# Hocki-Control.net
KiCad netlist of a schematic drawn in EAGLE
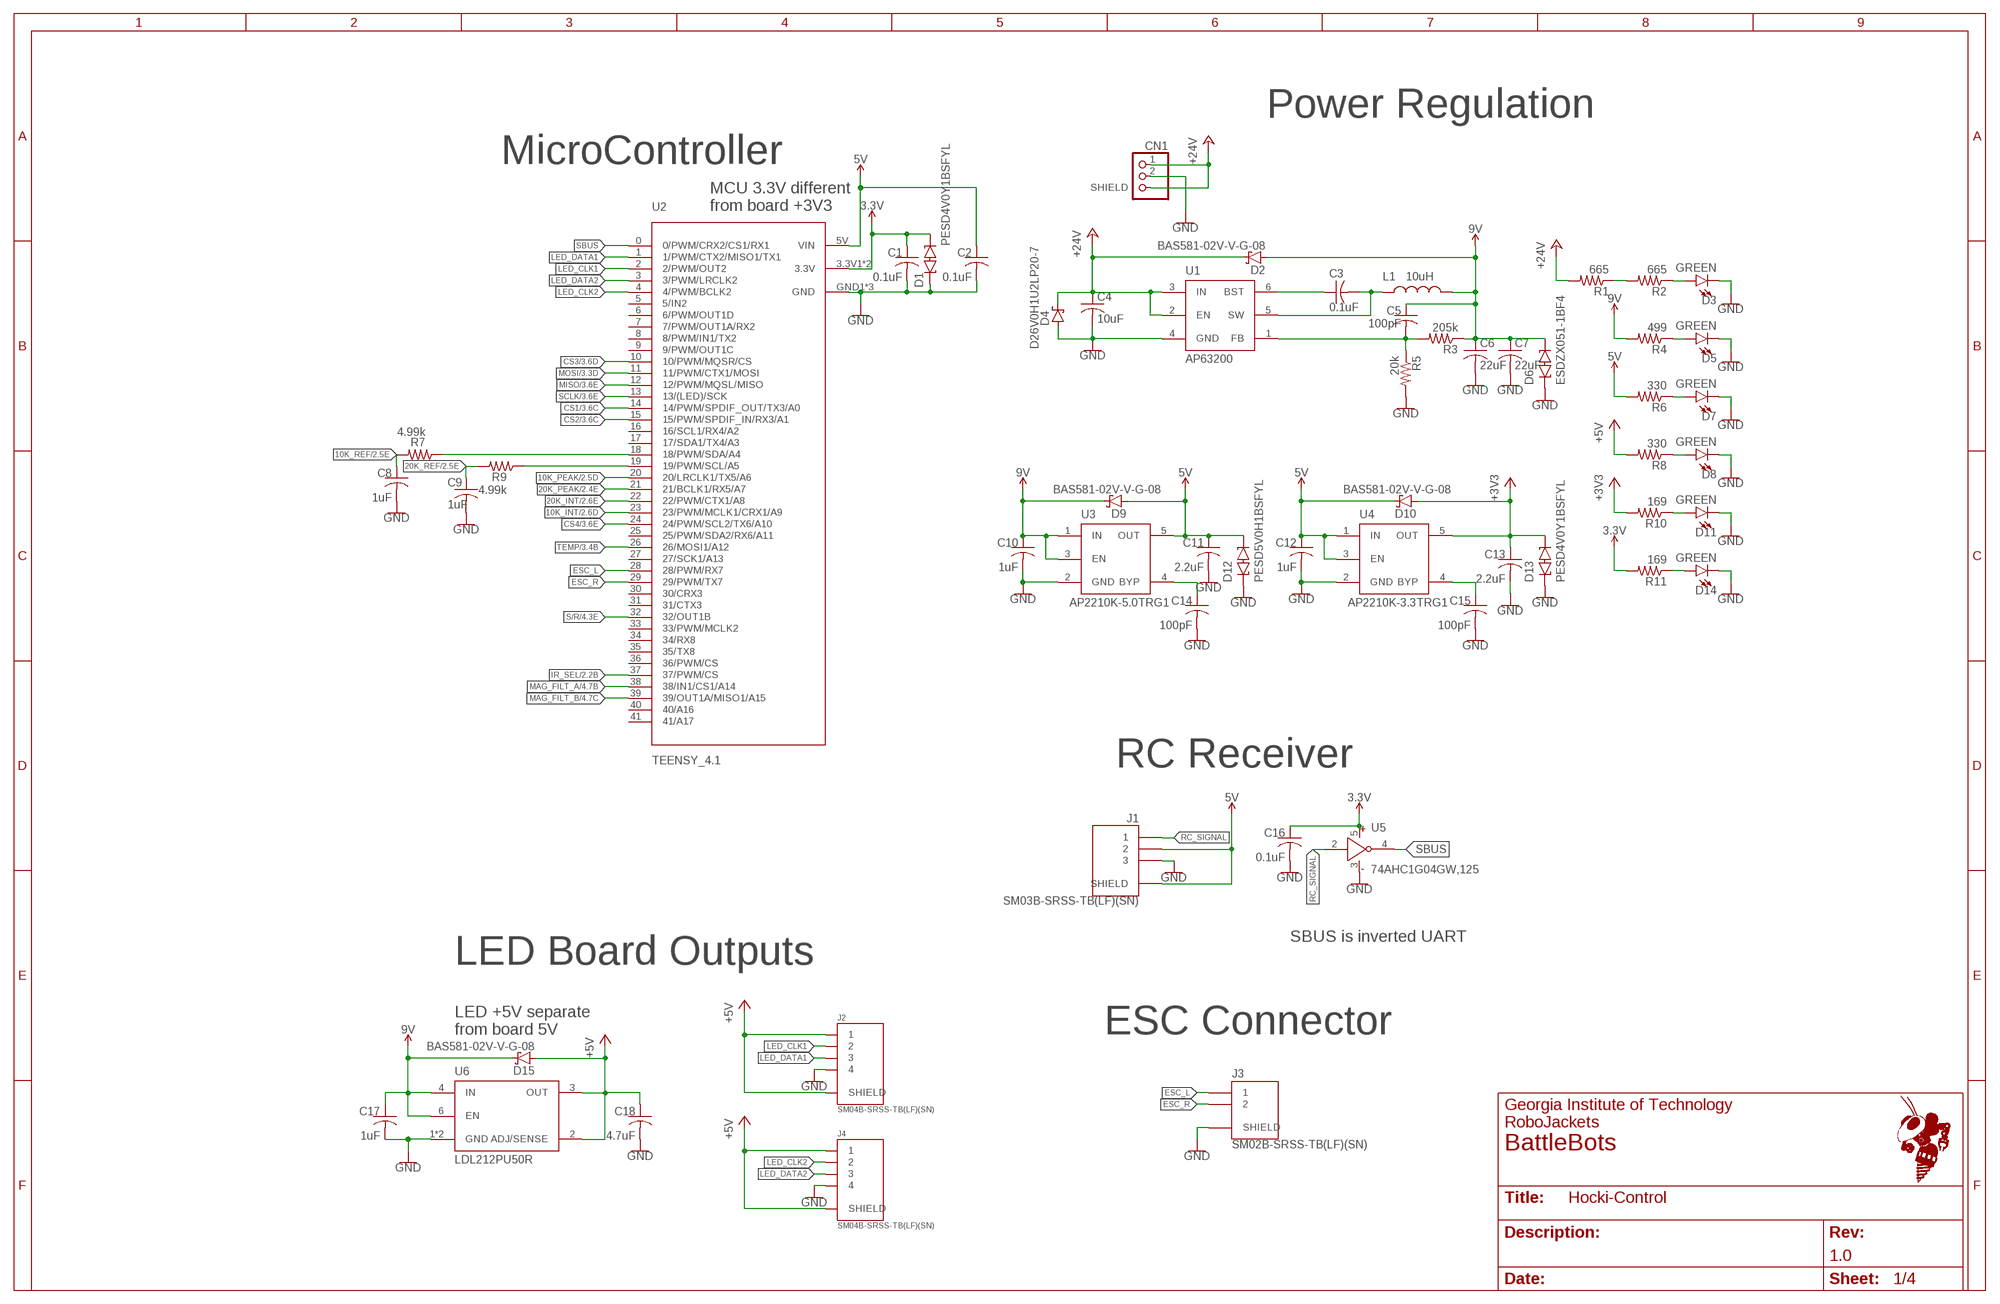
[diagram p0: schematic, sheet 1]
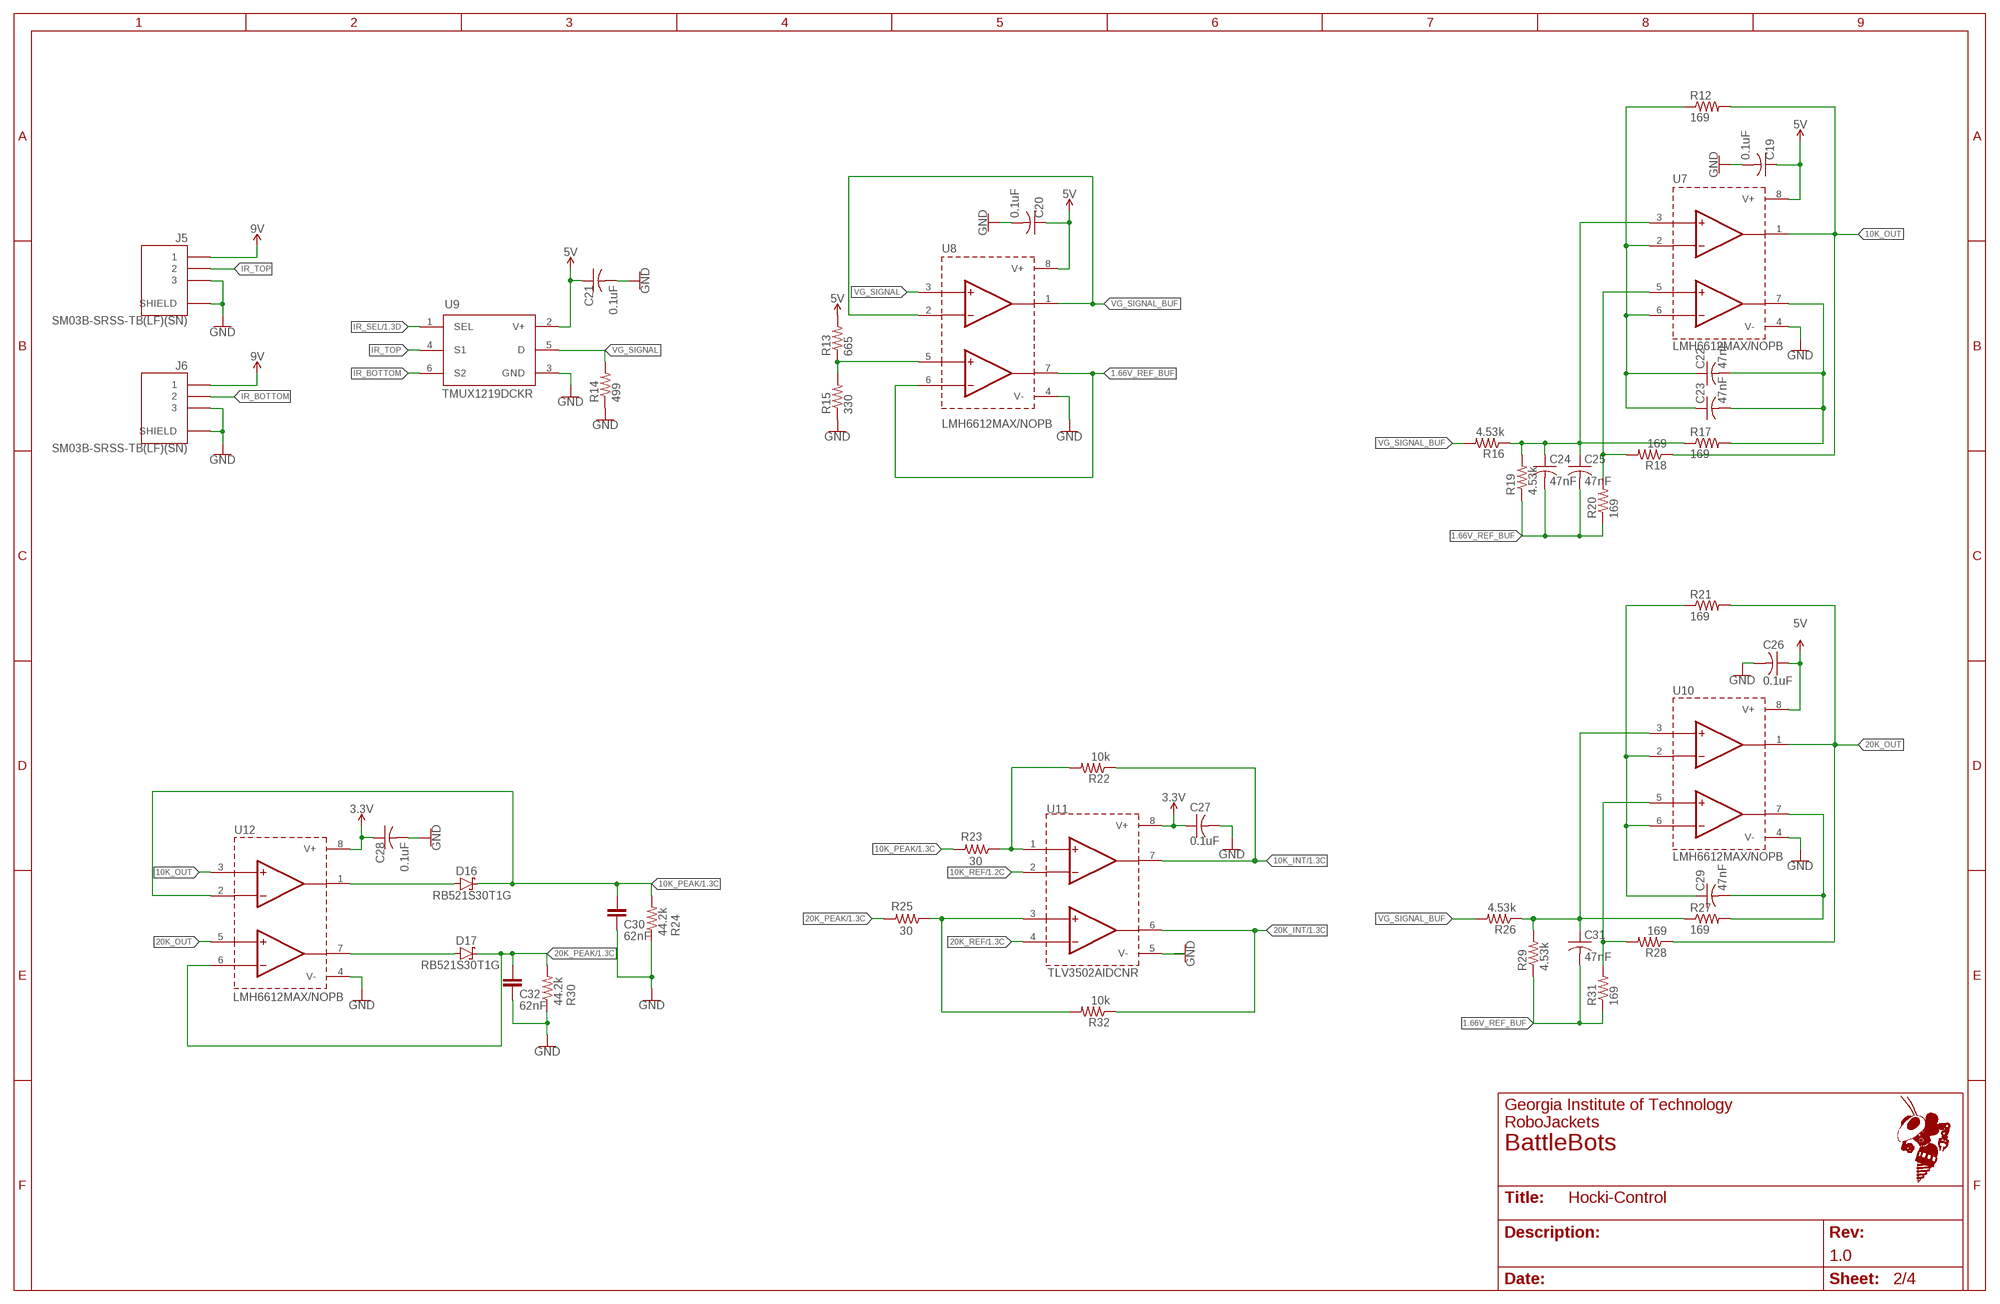
[diagram p1: schematic, sheet 2]
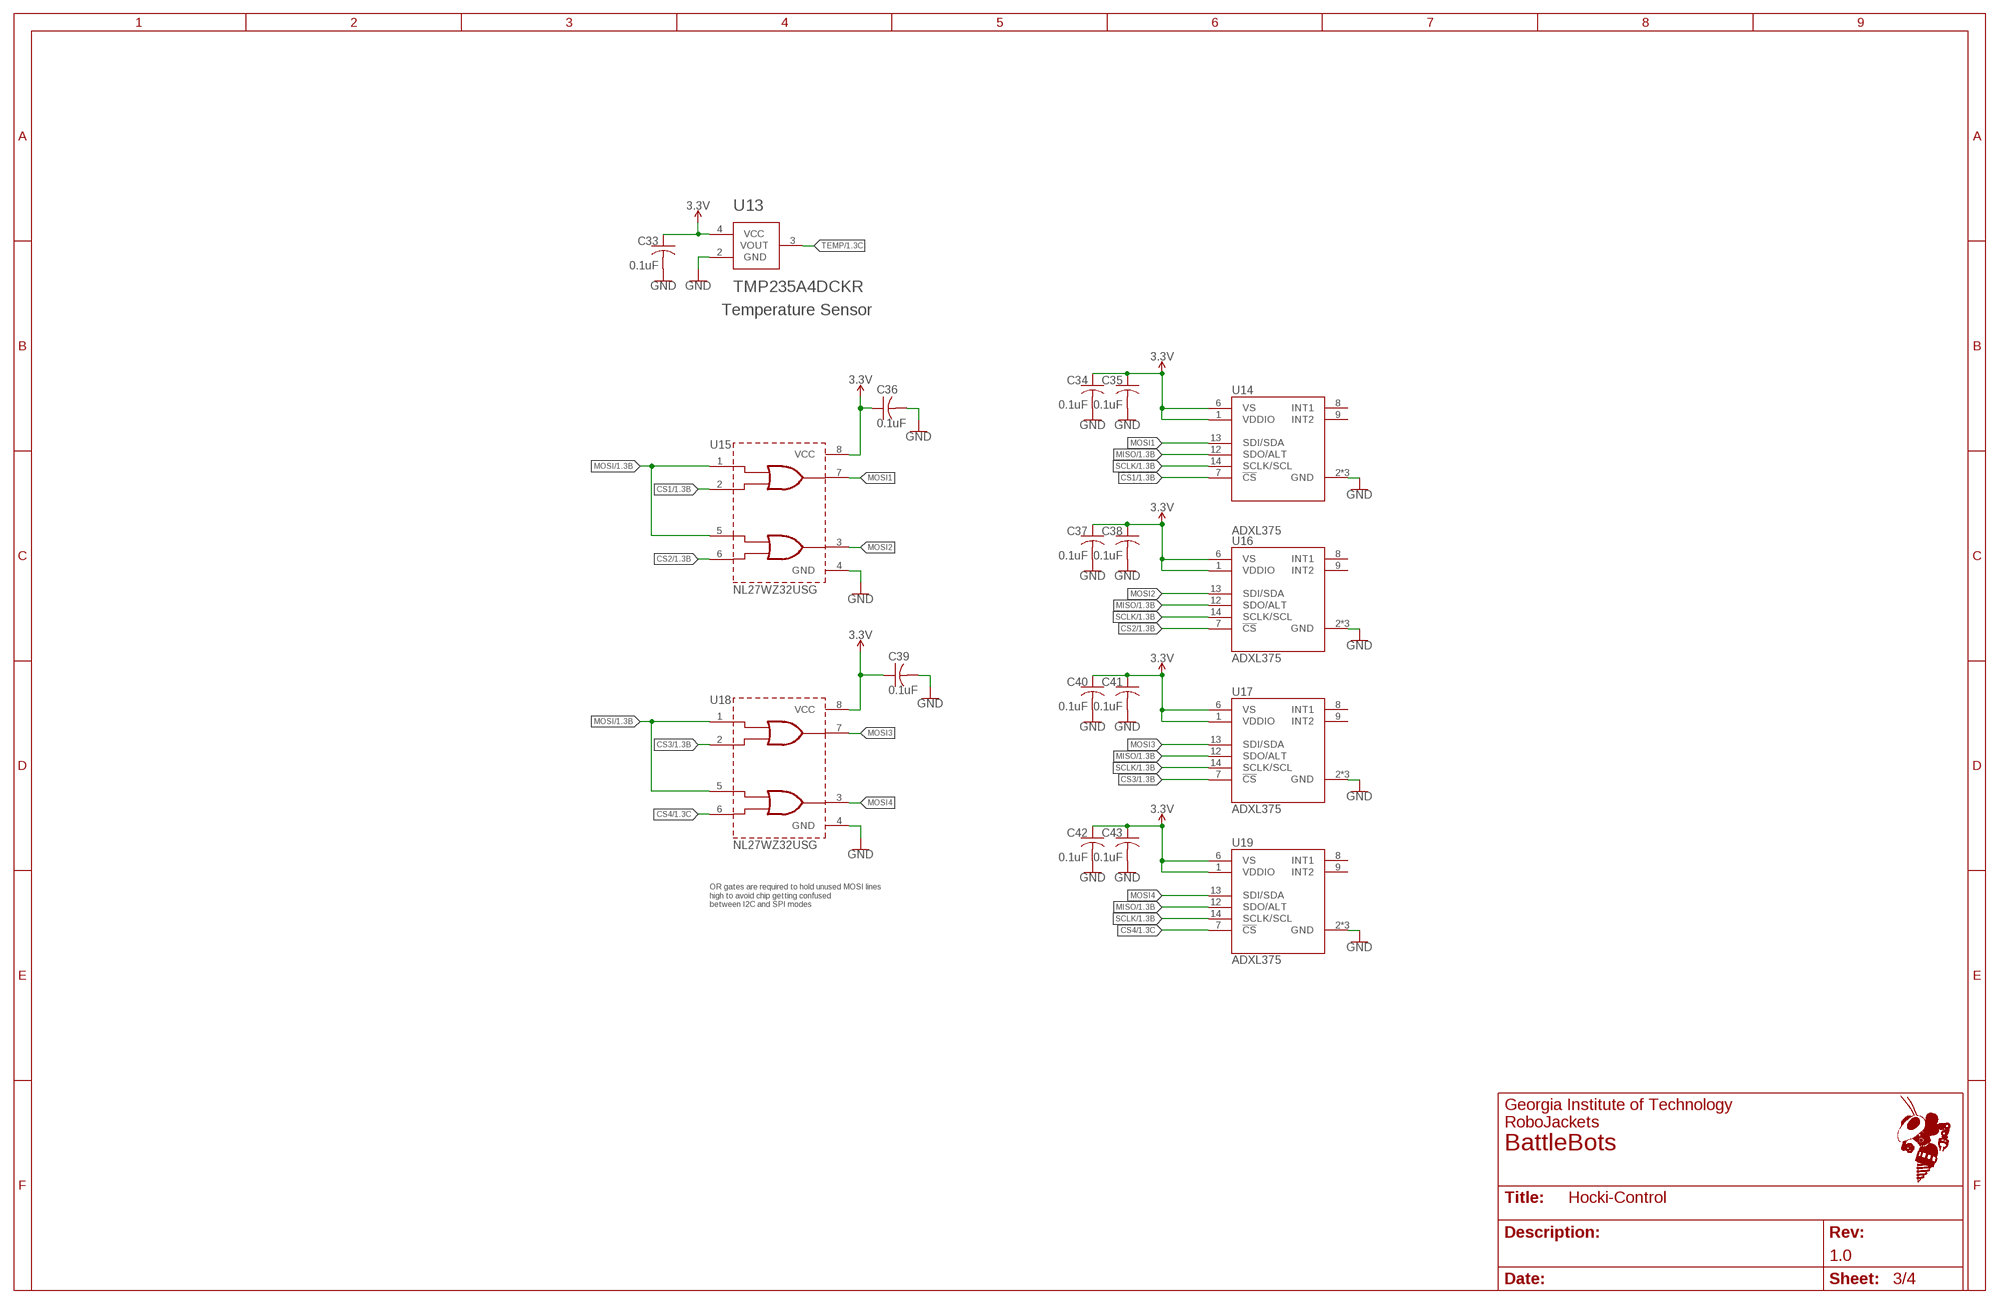
[diagram p2: schematic, sheet 3]
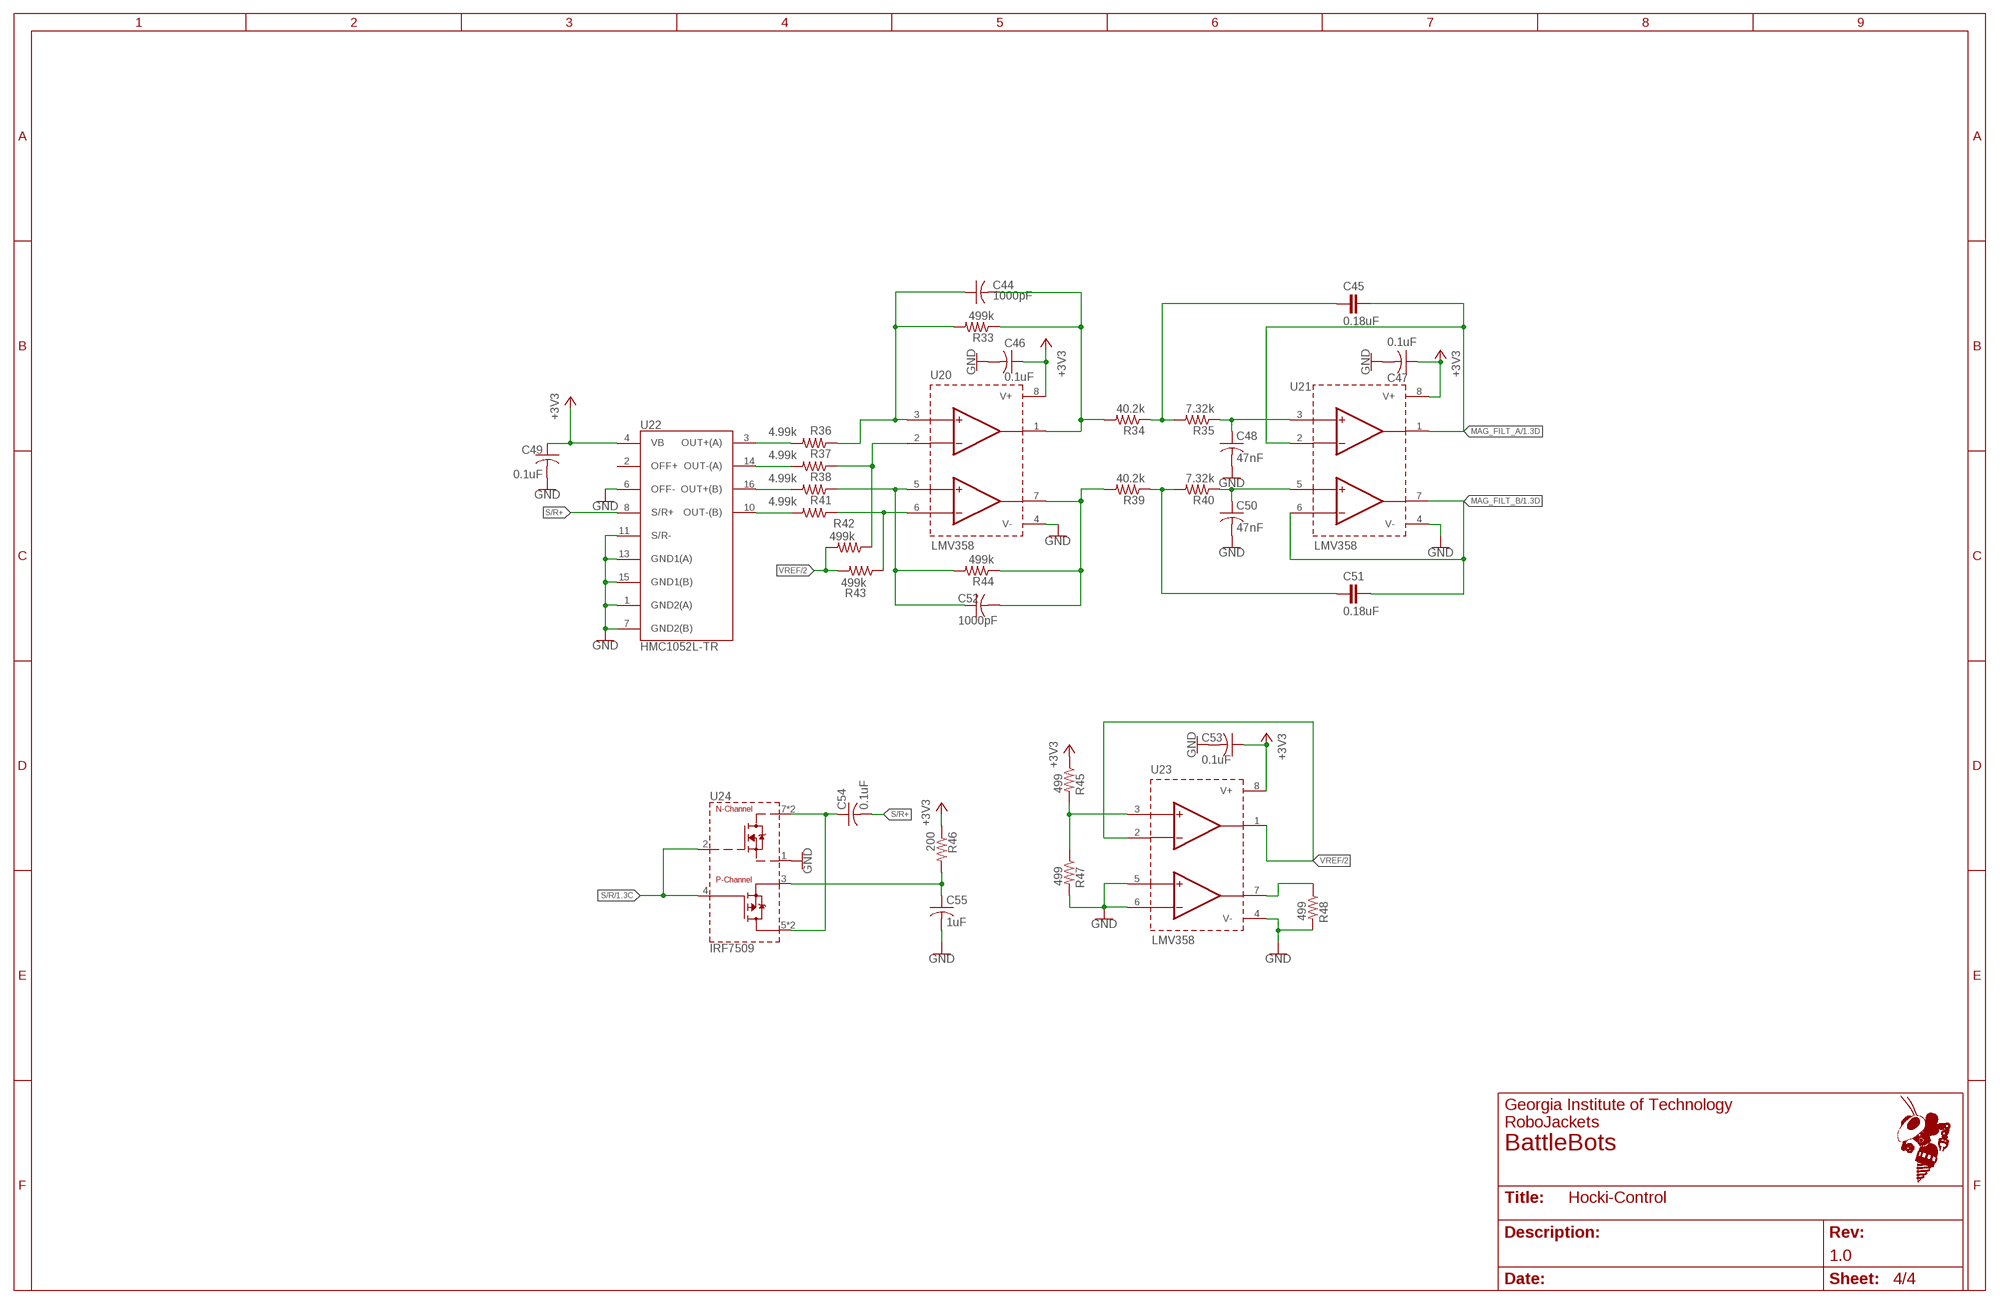
[diagram p3: schematic, sheet 4]

(export (version "E")
  (design (tool "Eeschema 10.0.6"))
  (components
    (comp (ref "C19")
      (value "0.1uF")
      (footprint "eagle-import:C0603")
      (libsource (lib "eagle-import") (part "C-USC0603"))
    )
    (comp (ref "C20")
      (value "0.1uF")
      (footprint "eagle-import:C0603")
      (libsource (lib "eagle-import") (part "C-USC0603"))
    )
    (comp (ref "C21")
      (value "0.1uF")
      (footprint "eagle-import:C0603")
      (libsource (lib "eagle-import") (part "C-USC0603"))
    )
    (comp (ref "C22")
      (value "47nF")
      (footprint "eagle-import:C1206")
      (libsource (lib "eagle-import") (part "C-USC1206"))
    )
    (comp (ref "C23")
      (value "47nF")
      (footprint "eagle-import:C1206")
      (libsource (lib "eagle-import") (part "C-USC1206"))
    )
    (comp (ref "C24")
      (value "47nF")
      (footprint "eagle-import:C1206")
      (libsource (lib "eagle-import") (part "C-USC1206"))
    )
    (comp (ref "C25")
      (value "47nF")
      (footprint "eagle-import:C1206")
      (libsource (lib "eagle-import") (part "C-USC1206"))
    )
    (comp (ref "C26")
      (value "0.1uF")
      (footprint "eagle-import:C0603")
      (libsource (lib "eagle-import") (part "C-USC0603"))
    )
    (comp (ref "C27")
      (value "0.1uF")
      (footprint "eagle-import:C0603")
      (libsource (lib "eagle-import") (part "C-USC0603"))
    )
    (comp (ref "C28")
      (value "0.1uF")
      (footprint "eagle-import:C0603")
      (libsource (lib "eagle-import") (part "C-USC0603"))
    )
    (comp (ref "C29")
      (value "47nF")
      (footprint "eagle-import:C1206")
      (libsource (lib "eagle-import") (part "C-USC1206"))
    )
    (comp (ref "C30")
      (value "62nF")
      (footprint "eagle-import:BFC241646203")
      (libsource (lib "eagle-import") (part "BFC241646203"))
    )
    (comp (ref "C31")
      (value "47nF")
      (footprint "eagle-import:C1206")
      (libsource (lib "eagle-import") (part "C-USC1206"))
    )
    (comp (ref "C32")
      (value "62nF")
      (footprint "eagle-import:BFC241646203")
      (libsource (lib "eagle-import") (part "BFC241646203"))
    )
    (comp (ref "D16")
      (value "RB521S30T1G")
      (footprint "eagle-import:SOD-523")
      (libsource (lib "eagle-import") (part "RB521S30T1G"))
    )
    (comp (ref "D17")
      (value "RB521S30T1G")
      (footprint "eagle-import:SOD-523")
      (libsource (lib "eagle-import") (part "RB521S30T1G"))
    )
    (comp (ref "J5")
      (value "SM03B-SRSS-TB(LF)(SN)")
      (footprint "eagle-import:SM03B-SRSS-TB(LF)(SN)")
      (libsource (lib "eagle-import") (part "SM03B-SRSS-TB(LF)(SN)"))
    )
    (comp (ref "J6")
      (value "SM03B-SRSS-TB(LF)(SN)")
      (footprint "eagle-import:SM03B-SRSS-TB(LF)(SN)")
      (libsource (lib "eagle-import") (part "SM03B-SRSS-TB(LF)(SN)"))
    )
    (comp (ref "R12")
      (value "169")
      (footprint "eagle-import:R0603")
      (libsource (lib "eagle-import") (part "R-US_R0603"))
    )
    (comp (ref "R13")
      (value "665")
      (footprint "eagle-import:R0603")
      (libsource (lib "eagle-import") (part "R-US_R0603"))
    )
    (comp (ref "R14")
      (value "499")
      (footprint "eagle-import:R0603")
      (libsource (lib "eagle-import") (part "R-US_R0603"))
    )
    (comp (ref "R15")
      (value "330")
      (footprint "eagle-import:R0603")
      (libsource (lib "eagle-import") (part "R-US_R0603"))
    )
    (comp (ref "R16")
      (value "4.53k")
      (footprint "eagle-import:R0603")
      (libsource (lib "eagle-import") (part "R-US_R0603"))
    )
    (comp (ref "R17")
      (value "169")
      (footprint "eagle-import:R0603")
      (libsource (lib "eagle-import") (part "R-US_R0603"))
    )
    (comp (ref "R18")
      (value "169")
      (footprint "eagle-import:R0603")
      (libsource (lib "eagle-import") (part "R-US_R0603"))
    )
    (comp (ref "R19")
      (value "4.53k")
      (footprint "eagle-import:R0603")
      (libsource (lib "eagle-import") (part "R-US_R0603"))
    )
    (comp (ref "R20")
      (value "169")
      (footprint "eagle-import:R0603")
      (libsource (lib "eagle-import") (part "R-US_R0603"))
    )
    (comp (ref "R21")
      (value "169")
      (footprint "eagle-import:R0603")
      (libsource (lib "eagle-import") (part "R-US_R0603"))
    )
    (comp (ref "R22")
      (value "10k")
      (footprint "eagle-import:R0603")
      (libsource (lib "eagle-import") (part "R-US_R0603"))
    )
    (comp (ref "R23")
      (value "30")
      (footprint "eagle-import:R0603")
      (libsource (lib "eagle-import") (part "R-US_R0603"))
    )
    (comp (ref "R24")
      (value "44.2k")
      (footprint "eagle-import:R0603")
      (libsource (lib "eagle-import") (part "R-US_R0603"))
    )
    (comp (ref "R25")
      (value "30")
      (footprint "eagle-import:R0603")
      (libsource (lib "eagle-import") (part "R-US_R0603"))
    )
    (comp (ref "R26")
      (value "4.53k")
      (footprint "eagle-import:R0603")
      (libsource (lib "eagle-import") (part "R-US_R0603"))
    )
    (comp (ref "R27")
      (value "169")
      (footprint "eagle-import:R0603")
      (libsource (lib "eagle-import") (part "R-US_R0603"))
    )
    (comp (ref "R28")
      (value "169")
      (footprint "eagle-import:R0603")
      (libsource (lib "eagle-import") (part "R-US_R0603"))
    )
    (comp (ref "R29")
      (value "4.53k")
      (footprint "eagle-import:R0603")
      (libsource (lib "eagle-import") (part "R-US_R0603"))
    )
    (comp (ref "R30")
      (value "44.2k")
      (footprint "eagle-import:R0603")
      (libsource (lib "eagle-import") (part "R-US_R0603"))
    )
    (comp (ref "R31")
      (value "169")
      (footprint "eagle-import:R0603")
      (libsource (lib "eagle-import") (part "R-US_R0603"))
    )
    (comp (ref "R32")
      (value "10k")
      (footprint "eagle-import:R0603")
      (libsource (lib "eagle-import") (part "R-US_R0603"))
    )
    (comp (ref "U7")
      (value "LMH6612MAX/NOPB")
      (footprint "eagle-import:8-SOIC")
      (libsource (lib "eagle-import") (part "LMH6612MAX/NOPB"))
    )
    (comp (ref "U8")
      (value "LMH6612MAX/NOPB")
      (footprint "eagle-import:8-SOIC")
      (libsource (lib "eagle-import") (part "LMH6612MAX/NOPB"))
    )
    (comp (ref "U9")
      (value "TMUX1219DCKR")
      (footprint "eagle-import:SOT-363")
      (libsource (lib "eagle-import") (part "TMUX1219DCKR"))
    )
    (comp (ref "U10")
      (value "LMH6612MAX/NOPB")
      (footprint "eagle-import:8-SOIC")
      (libsource (lib "eagle-import") (part "LMH6612MAX/NOPB"))
    )
    (comp (ref "U11")
      (value "TLV3502AIDCNR")
      (footprint "eagle-import:SOT-23-8")
      (libsource (lib "eagle-import") (part "TLV3502AIDCNR"))
    )
    (comp (ref "U12")
      (value "LMH6612MAX/NOPB")
      (footprint "eagle-import:8-SOIC")
      (libsource (lib "eagle-import") (part "LMH6612MAX/NOPB"))
    )
    (comp (ref "C44")
      (value "1000pF")
      (footprint "eagle-import:C0805")
      (libsource (lib "eagle-import") (part "C-USC0805"))
    )
    (comp (ref "C45")
      (value "0.18uF")
      (footprint "eagle-import:ECH-U1H184GX9")
      (libsource (lib "eagle-import") (part "ECH-U1H184GX9"))
    )
    (comp (ref "C46")
      (value "0.1uF")
      (footprint "eagle-import:C0603")
      (libsource (lib "eagle-import") (part "C-USC0603"))
    )
    (comp (ref "C47")
      (value "0.1uF")
      (footprint "eagle-import:C0603")
      (libsource (lib "eagle-import") (part "C-USC0603"))
    )
    (comp (ref "C48")
      (value "47nF")
      (footprint "eagle-import:C1206")
      (libsource (lib "eagle-import") (part "C-USC1206"))
    )
    (comp (ref "C49")
      (value "0.1uF")
      (footprint "eagle-import:C0603")
      (libsource (lib "eagle-import") (part "C-USC0603"))
    )
    (comp (ref "C50")
      (value "47nF")
      (footprint "eagle-import:C1206")
      (libsource (lib "eagle-import") (part "C-USC1206"))
    )
    (comp (ref "C51")
      (value "0.18uF")
      (footprint "eagle-import:ECH-U1H184GX9")
      (libsource (lib "eagle-import") (part "ECH-U1H184GX9"))
    )
    (comp (ref "C52")
      (value "1000pF")
      (footprint "eagle-import:C0805")
      (libsource (lib "eagle-import") (part "C-USC0805"))
    )
    (comp (ref "C53")
      (value "0.1uF")
      (footprint "eagle-import:C0603")
      (libsource (lib "eagle-import") (part "C-USC0603"))
    )
    (comp (ref "C54")
      (value "0.1uF")
      (footprint "eagle-import:C0603")
      (libsource (lib "eagle-import") (part "C-USC0603"))
    )
    (comp (ref "C55")
      (value "1uF")
      (footprint "eagle-import:C0603")
      (libsource (lib "eagle-import") (part "C-USC0603"))
    )
    (comp (ref "R33")
      (value "499k")
      (footprint "eagle-import:R0603")
      (libsource (lib "eagle-import") (part "R-US_R0603"))
    )
    (comp (ref "R34")
      (value "40.2k")
      (footprint "eagle-import:R0603")
      (libsource (lib "eagle-import") (part "R-US_R0603"))
    )
    (comp (ref "R35")
      (value "7.32k")
      (footprint "eagle-import:R0603")
      (libsource (lib "eagle-import") (part "R-US_R0603"))
    )
    (comp (ref "R36")
      (value "4.99k")
      (footprint "eagle-import:R0603")
      (libsource (lib "eagle-import") (part "R-US_R0603"))
    )
    (comp (ref "R37")
      (value "4.99k")
      (footprint "eagle-import:R0603")
      (libsource (lib "eagle-import") (part "R-US_R0603"))
    )
    (comp (ref "R38")
      (value "4.99k")
      (footprint "eagle-import:R0603")
      (libsource (lib "eagle-import") (part "R-US_R0603"))
    )
    (comp (ref "R39")
      (value "40.2k")
      (footprint "eagle-import:R0603")
      (libsource (lib "eagle-import") (part "R-US_R0603"))
    )
    (comp (ref "R40")
      (value "7.32k")
      (footprint "eagle-import:R0603")
      (libsource (lib "eagle-import") (part "R-US_R0603"))
    )
    (comp (ref "R41")
      (value "4.99k")
      (footprint "eagle-import:R0603")
      (libsource (lib "eagle-import") (part "R-US_R0603"))
    )
    (comp (ref "R42")
      (value "499k")
      (footprint "eagle-import:R0603")
      (libsource (lib "eagle-import") (part "R-US_R0603"))
    )
    (comp (ref "R43")
      (value "499k")
      (footprint "eagle-import:R0603")
      (libsource (lib "eagle-import") (part "R-US_R0603"))
    )
    (comp (ref "R44")
      (value "499k")
      (footprint "eagle-import:R0603")
      (libsource (lib "eagle-import") (part "R-US_R0603"))
    )
    (comp (ref "R45")
      (value "499")
      (footprint "eagle-import:R0603")
      (libsource (lib "eagle-import") (part "R-US_R0603"))
    )
    (comp (ref "R46")
      (value "200")
      (footprint "eagle-import:R0603")
      (libsource (lib "eagle-import") (part "R-US_R0603"))
    )
    (comp (ref "R47")
      (value "499")
      (footprint "eagle-import:R0603")
      (libsource (lib "eagle-import") (part "R-US_R0603"))
    )
    (comp (ref "R48")
      (value "499")
      (footprint "eagle-import:R0603")
      (libsource (lib "eagle-import") (part "R-US_R0603"))
    )
    (comp (ref "U20")
      (value "LMV358")
      (footprint "eagle-import:8-SOIC")
      (libsource (lib "eagle-import") (part "LMV358"))
    )
    (comp (ref "U21")
      (value "LMV358")
      (footprint "eagle-import:8-SOIC")
      (libsource (lib "eagle-import") (part "LMV358"))
    )
    (comp (ref "U22")
      (value "HMC1052L-TR")
      (footprint "eagle-import:16-LCC")
      (libsource (lib "eagle-import") (part "HMC1052L-TR"))
    )
    (comp (ref "U23")
      (value "LMV358")
      (footprint "eagle-import:8-SOIC")
      (libsource (lib "eagle-import") (part "LMV358"))
    )
    (comp (ref "U24")
      (value "IRF7509")
      (footprint "eagle-import:MICRO8")
      (libsource (lib "eagle-import") (part "IRF7509"))
    )
    (comp (ref "C33")
      (value "0.1uF")
      (footprint "eagle-import:C0603")
      (libsource (lib "eagle-import") (part "C-USC0603"))
    )
    (comp (ref "C34")
      (value "0.1uF")
      (footprint "eagle-import:C0603")
      (libsource (lib "eagle-import") (part "C-USC0603"))
    )
    (comp (ref "C35")
      (value "0.1uF")
      (footprint "eagle-import:C0603")
      (libsource (lib "eagle-import") (part "C-USC0603"))
    )
    (comp (ref "C36")
      (value "0.1uF")
      (footprint "eagle-import:C0603")
      (libsource (lib "eagle-import") (part "C-USC0603"))
    )
    (comp (ref "C37")
      (value "0.1uF")
      (footprint "eagle-import:C0603")
      (libsource (lib "eagle-import") (part "C-USC0603"))
    )
    (comp (ref "C38")
      (value "0.1uF")
      (footprint "eagle-import:C0603")
      (libsource (lib "eagle-import") (part "C-USC0603"))
    )
    (comp (ref "C39")
      (value "0.1uF")
      (footprint "eagle-import:C0603")
      (libsource (lib "eagle-import") (part "C-USC0603"))
    )
    (comp (ref "C40")
      (value "0.1uF")
      (footprint "eagle-import:C0603")
      (libsource (lib "eagle-import") (part "C-USC0603"))
    )
    (comp (ref "C41")
      (value "0.1uF")
      (footprint "eagle-import:C0603")
      (libsource (lib "eagle-import") (part "C-USC0603"))
    )
    (comp (ref "C42")
      (value "0.1uF")
      (footprint "eagle-import:C0603")
      (libsource (lib "eagle-import") (part "C-USC0603"))
    )
    (comp (ref "C43")
      (value "0.1uF")
      (footprint "eagle-import:C0603")
      (libsource (lib "eagle-import") (part "C-USC0603"))
    )
    (comp (ref "U13")
      (value "TMP235A4DCKR")
      (footprint "eagle-import:SOT-353")
      (libsource (lib "eagle-import") (part "TMP235A4DCKR"))
    )
    (comp (ref "U14")
      (value "ADXL375")
      (footprint "eagle-import:14-LGA")
      (libsource (lib "eagle-import") (part "ADXL375"))
    )
    (comp (ref "U15")
      (value "NL27WZ32USG")
      (footprint "eagle-import:US8")
      (libsource (lib "eagle-import") (part "NL27WZ32USG"))
    )
    (comp (ref "U16")
      (value "ADXL375")
      (footprint "eagle-import:14-LGA")
      (libsource (lib "eagle-import") (part "ADXL375"))
    )
    (comp (ref "U17")
      (value "ADXL375")
      (footprint "eagle-import:14-LGA")
      (libsource (lib "eagle-import") (part "ADXL375"))
    )
    (comp (ref "U18")
      (value "NL27WZ32USG")
      (footprint "eagle-import:US8")
      (libsource (lib "eagle-import") (part "NL27WZ32USG"))
    )
    (comp (ref "U19")
      (value "ADXL375")
      (footprint "eagle-import:14-LGA")
      (libsource (lib "eagle-import") (part "ADXL375"))
    )
    (comp (ref "C1")
      (value "0.1uF")
      (footprint "eagle-import:C0603")
      (libsource (lib "eagle-import") (part "C-USC0603"))
    )
    (comp (ref "C2")
      (value "0.1uF")
      (footprint "eagle-import:C0603")
      (libsource (lib "eagle-import") (part "C-USC0603"))
    )
    (comp (ref "C3")
      (value "0.1uF")
      (footprint "eagle-import:C0603")
      (libsource (lib "eagle-import") (part "C-USC0603"))
    )
    (comp (ref "C4")
      (value "10uF")
      (footprint "eagle-import:C1206")
      (libsource (lib "eagle-import") (part "C-USC1206"))
    )
    (comp (ref "C5")
      (value "100pF")
      (footprint "eagle-import:C0603")
      (libsource (lib "eagle-import") (part "C-USC0603"))
    )
    (comp (ref "C6")
      (value "22uF")
      (footprint "eagle-import:C1206")
      (libsource (lib "eagle-import") (part "C-USC1206"))
    )
    (comp (ref "C7")
      (value "22uF")
      (footprint "eagle-import:C1206")
      (libsource (lib "eagle-import") (part "C-USC1206"))
    )
    (comp (ref "C8")
      (value "1uF")
      (footprint "eagle-import:C0603")
      (libsource (lib "eagle-import") (part "C-USC0603"))
    )
    (comp (ref "C9")
      (value "1uF")
      (footprint "eagle-import:C0603")
      (libsource (lib "eagle-import") (part "C-USC0603"))
    )
    (comp (ref "C10")
      (value "1uF")
      (footprint "eagle-import:C0603")
      (libsource (lib "eagle-import") (part "C-USC0603"))
    )
    (comp (ref "C11")
      (value "2.2uF")
      (footprint "eagle-import:C0603")
      (libsource (lib "eagle-import") (part "C-USC0603"))
    )
    (comp (ref "C12")
      (value "1uF")
      (footprint "eagle-import:C0603")
      (libsource (lib "eagle-import") (part "C-USC0603"))
    )
    (comp (ref "C13")
      (value "2.2uF")
      (footprint "eagle-import:C0603")
      (libsource (lib "eagle-import") (part "C-USC0603"))
    )
    (comp (ref "C14")
      (value "100pF")
      (footprint "eagle-import:C0603")
      (libsource (lib "eagle-import") (part "C-USC0603"))
    )
    (comp (ref "C15")
      (value "100pF")
      (footprint "eagle-import:C0603")
      (libsource (lib "eagle-import") (part "C-USC0603"))
    )
    (comp (ref "C16")
      (value "0.1uF")
      (footprint "eagle-import:C0603")
      (libsource (lib "eagle-import") (part "C-USC0603"))
    )
    (comp (ref "C17")
      (value "1uF")
      (footprint "eagle-import:C0603")
      (libsource (lib "eagle-import") (part "C-USC0603"))
    )
    (comp (ref "C18")
      (value "4.7uF")
      (footprint "eagle-import:C0603")
      (libsource (lib "eagle-import") (part "C-USC0603"))
    )
    (comp (ref "CN1")
      (value "JST_2PIN")
      (footprint "eagle-import:JST-PH-2-SMT")
      (libsource (lib "eagle-import") (part "JST_2PIN"))
    )
    (comp (ref "D1")
      (value "PESD4V0Y1BSFYL")
      (footprint "eagle-import:DSN0603-2")
      (libsource (lib "eagle-import") (part "PESD4V0Y1BSFYL"))
    )
    (comp (ref "D2")
      (value "BAS581-02V-V-G-08")
      (footprint "eagle-import:SOD-523")
      (libsource (lib "eagle-import") (part "BAS581-02V-V-G-08"))
    )
    (comp (ref "D3")
      (value "GREEN")
      (footprint "eagle-import:LED-0603")
      (libsource (lib "eagle-import") (part "LED-GREEN0603"))
    )
    (comp (ref "D4")
      (value "D26V0H1U2LP20-7")
      (footprint "eagle-import:D26V0H1U2LP20-7")
      (libsource (lib "eagle-import") (part "D26V0H1U2LP20-7"))
    )
    (comp (ref "D5")
      (value "GREEN")
      (footprint "eagle-import:LED-0603")
      (libsource (lib "eagle-import") (part "LED-GREEN0603"))
    )
    (comp (ref "D6")
      (value "ESDZX051-1BF4")
      (footprint "eagle-import:DSN0603-2")
      (libsource (lib "eagle-import") (part "ESDZX051-1BF4"))
    )
    (comp (ref "D7")
      (value "GREEN")
      (footprint "eagle-import:LED-0603")
      (libsource (lib "eagle-import") (part "LED-GREEN0603"))
    )
    (comp (ref "D8")
      (value "GREEN")
      (footprint "eagle-import:LED-0603")
      (libsource (lib "eagle-import") (part "LED-GREEN0603"))
    )
    (comp (ref "D9")
      (value "BAS581-02V-V-G-08")
      (footprint "eagle-import:SOD-523")
      (libsource (lib "eagle-import") (part "BAS581-02V-V-G-08"))
    )
    (comp (ref "D10")
      (value "BAS581-02V-V-G-08")
      (footprint "eagle-import:SOD-523")
      (libsource (lib "eagle-import") (part "BAS581-02V-V-G-08"))
    )
    (comp (ref "D11")
      (value "GREEN")
      (footprint "eagle-import:LED-0603")
      (libsource (lib "eagle-import") (part "LED-GREEN0603"))
    )
    (comp (ref "D12")
      (value "PESD5V0H1BSFYL")
      (footprint "eagle-import:DSN0603-2")
      (libsource (lib "eagle-import") (part "PESD5V0H1BSFYL"))
    )
    (comp (ref "D13")
      (value "PESD4V0Y1BSFYL")
      (footprint "eagle-import:DSN0603-2")
      (libsource (lib "eagle-import") (part "PESD4V0Y1BSFYL"))
    )
    (comp (ref "D14")
      (value "GREEN")
      (footprint "eagle-import:LED-0603")
      (libsource (lib "eagle-import") (part "LED-GREEN0603"))
    )
    (comp (ref "D15")
      (value "BAS581-02V-V-G-08")
      (footprint "eagle-import:SOD-523")
      (libsource (lib "eagle-import") (part "BAS581-02V-V-G-08"))
    )
    (comp (ref "J1")
      (value "SM03B-SRSS-TB(LF)(SN)")
      (footprint "eagle-import:SM03B-SRSS-TB(LF)(SN)")
      (libsource (lib "eagle-import") (part "SM03B-SRSS-TB(LF)(SN)"))
    )
    (comp (ref "J2")
      (value "SM04B-SRSS-TB(LF)(SN)")
      (footprint "eagle-import:SM04B-SRSS-TB(LF)(SN)")
      (libsource (lib "eagle-import") (part "SM04B-SRSS-TB(LF)(SN)"))
    )
    (comp (ref "J3")
      (value "SM02B-SRSS-TB(LF)(SN)")
      (footprint "eagle-import:SM02B-SRSS-TB(LF)(SN)")
      (libsource (lib "eagle-import") (part "SM02B-SRSS-TB(LF)(SN)"))
    )
    (comp (ref "J4")
      (value "SM04B-SRSS-TB(LF)(SN)")
      (footprint "eagle-import:SM04B-SRSS-TB(LF)(SN)")
      (libsource (lib "eagle-import") (part "SM04B-SRSS-TB(LF)(SN)"))
    )
    (comp (ref "L1")
      (value "10uH")
      (footprint "eagle-import:LQH5BPN100M38L")
      (libsource (lib "eagle-import") (part "LQH5BPN100M38L"))
    )
    (comp (ref "R1")
      (value "665")
      (footprint "eagle-import:R0603")
      (libsource (lib "eagle-import") (part "R-US_R0603"))
    )
    (comp (ref "R2")
      (value "665")
      (footprint "eagle-import:R0603")
      (libsource (lib "eagle-import") (part "R-US_R0603"))
    )
    (comp (ref "R3")
      (value "205k")
      (footprint "eagle-import:R0603")
      (libsource (lib "eagle-import") (part "R-US_R0603"))
    )
    (comp (ref "R4")
      (value "499")
      (footprint "eagle-import:R0603")
      (libsource (lib "eagle-import") (part "R-US_R0603"))
    )
    (comp (ref "R5")
      (value "20k")
      (footprint "eagle-import:R0603")
      (libsource (lib "eagle-import") (part "R-US_R0603"))
    )
    (comp (ref "R6")
      (value "330")
      (footprint "eagle-import:R0603")
      (libsource (lib "eagle-import") (part "R-US_R0603"))
    )
    (comp (ref "R7")
      (value "4.99k")
      (footprint "eagle-import:R0603")
      (libsource (lib "eagle-import") (part "R-US_R0603"))
    )
    (comp (ref "R8")
      (value "330")
      (footprint "eagle-import:R0603")
      (libsource (lib "eagle-import") (part "R-US_R0603"))
    )
    (comp (ref "R9")
      (value "4.99k")
      (footprint "eagle-import:R0603")
      (libsource (lib "eagle-import") (part "R-US_R0603"))
    )
    (comp (ref "R10")
      (value "169")
      (footprint "eagle-import:R0603")
      (libsource (lib "eagle-import") (part "R-US_R0603"))
    )
    (comp (ref "R11")
      (value "169")
      (footprint "eagle-import:R0603")
      (libsource (lib "eagle-import") (part "R-US_R0603"))
    )
    (comp (ref "U1")
      (value "AP63200")
      (footprint "eagle-import:SOT-23-6")
      (libsource (lib "eagle-import") (part "AP63200"))
    )
    (comp (ref "U2")
      (value "TEENSY_4.1")
      (footprint "eagle-import:TEENSY_4.1")
      (libsource (lib "eagle-import") (part "TEENSY_4.1"))
    )
    (comp (ref "U3")
      (value "AP2210K-5.0TRG1")
      (footprint "eagle-import:SOT-23-5")
      (libsource (lib "eagle-import") (part "AP2210K-TRG15.0"))
    )
    (comp (ref "U4")
      (value "AP2210K-3.3TRG1")
      (footprint "eagle-import:SOT-23-5")
      (libsource (lib "eagle-import") (part "AP2210K-TRG13.3"))
    )
    (comp (ref "U5")
      (value "74AHC1G04GW,125")
      (footprint "eagle-import:SOT-353")
      (libsource (lib "eagle-import") (part "74AHC1G04GW,125"))
    )
    (comp (ref "U6")
      (value "LDL212PU50R")
      (footprint "eagle-import:DFN6(3X3)")
      (libsource (lib "eagle-import") (part "LDL212PU50R"))
    )
  )
  (nets
    (net (code "1") (name "+3V3") (class "Default")
      (node (ref "C13") (pin "1") (pinfunction "1_1") (pintype "passive"))
      (node (ref "C46") (pin "1") (pinfunction "1_1") (pintype "passive"))
      (node (ref "C47") (pin "1") (pinfunction "1_1") (pintype "passive"))
      (node (ref "C49") (pin "1") (pinfunction "1_1") (pintype "passive"))
      (node (ref "C53") (pin "1") (pinfunction "1_1") (pintype "passive"))
      (node (ref "D10") (pin "2") (pinfunction "A_2") (pintype "passive"))
      (node (ref "D13") (pin "C2") (pinfunction "C2_C2") (pintype "passive"))
      (node (ref "R10") (pin "2") (pinfunction "2_2") (pintype "passive"))
      (node (ref "R45") (pin "1") (pinfunction "1_1") (pintype "passive"))
      (node (ref "R46") (pin "1") (pinfunction "1_1") (pintype "passive"))
      (node (ref "U20") (pin "8") (pinfunction "V+_8") (pintype "passive"))
      (node (ref "U21") (pin "8") (pinfunction "V+_8") (pintype "passive"))
      (node (ref "U22") (pin "4") (pinfunction "VB_4") (pintype "passive"))
      (node (ref "U23") (pin "8") (pinfunction "V+_8") (pintype "passive"))
      (node (ref "U4") (pin "5") (pinfunction "OUT_5") (pintype "passive"))
    )
    (net (code "2") (name "+5V") (class "Default")
      (node (ref "C18") (pin "1") (pinfunction "1_1") (pintype "passive"))
      (node (ref "D15") (pin "2") (pinfunction "A_2") (pintype "passive"))
      (node (ref "J2") (pin "1") (pinfunction "1_1") (pintype "passive"))
      (node (ref "J2") (pin "S1") (pinfunction "SHIELD_S1") (pintype "passive"))
      (node (ref "J2") (pin "S2") (pinfunction "SHIELD_S2") (pintype "passive"))
      (node (ref "J4") (pin "1") (pinfunction "1_1") (pintype "passive"))
      (node (ref "J4") (pin "S1") (pinfunction "SHIELD_S1") (pintype "passive"))
      (node (ref "J4") (pin "S2") (pinfunction "SHIELD_S2") (pintype "passive"))
      (node (ref "R8") (pin "2") (pinfunction "2_2") (pintype "passive"))
      (node (ref "U6") (pin "2") (pinfunction "ADJ/SENSE_2") (pintype "bidirectional"))
      (node (ref "U6") (pin "3") (pinfunction "OUT_3") (pintype "passive"))
    )
    (net (code "3") (name "+24V") (class "Default")
      (node (ref "C4") (pin "1") (pinfunction "1_1") (pintype "passive"))
      (node (ref "CN1") (pin "1") (pinfunction "1_1") (pintype "passive"))
      (node (ref "CN1") (pin "NC1") (pinfunction "SHIELD_NC1") (pintype "passive"))
      (node (ref "CN1") (pin "NC2") (pinfunction "SHIELD_NC2") (pintype "passive"))
      (node (ref "D2") (pin "1") (pinfunction "C_1") (pintype "passive"))
      (node (ref "D4") (pin "1") (pinfunction "C_1") (pintype "passive"))
      (node (ref "R1") (pin "2") (pinfunction "2_2") (pintype "passive"))
      (node (ref "U1") (pin "2") (pinfunction "EN_2") (pintype "passive"))
      (node (ref "U1") (pin "3") (pinfunction "IN_3") (pintype "passive"))
    )
    (net (code "4") (name "1.66V_REF_BUF") (class "Default")
      (node (ref "C24") (pin "2") (pinfunction "2_2") (pintype "passive"))
      (node (ref "C25") (pin "2") (pinfunction "2_2") (pintype "passive"))
      (node (ref "C31") (pin "2") (pinfunction "2_2") (pintype "passive"))
      (node (ref "R19") (pin "1") (pinfunction "1_1") (pintype "passive"))
      (node (ref "R20") (pin "1") (pinfunction "1_1") (pintype "passive"))
      (node (ref "R29") (pin "1") (pinfunction "1_1") (pintype "passive"))
      (node (ref "R31") (pin "1") (pinfunction "1_1") (pintype "passive"))
      (node (ref "U8") (pin "6") (pinfunction "INB-_6") (pintype "passive"))
      (node (ref "U8") (pin "7") (pinfunction "OUTB_7") (pintype "passive"))
    )
    (net (code "5") (name "3.3V") (class "Default")
      (node (ref "C1") (pin "1") (pinfunction "1_1") (pintype "passive"))
      (node (ref "C16") (pin "1") (pinfunction "1_1") (pintype "passive"))
      (node (ref "C27") (pin "1") (pinfunction "1_1") (pintype "passive"))
      (node (ref "C28") (pin "1") (pinfunction "1_1") (pintype "passive"))
      (node (ref "C33") (pin "1") (pinfunction "1_1") (pintype "passive"))
      (node (ref "C34") (pin "1") (pinfunction "1_1") (pintype "passive"))
      (node (ref "C35") (pin "1") (pinfunction "1_1") (pintype "passive"))
      (node (ref "C36") (pin "1") (pinfunction "1_1") (pintype "passive"))
      (node (ref "C37") (pin "1") (pinfunction "1_1") (pintype "passive"))
      (node (ref "C38") (pin "1") (pinfunction "1_1") (pintype "passive"))
      (node (ref "C39") (pin "1") (pinfunction "1_1") (pintype "passive"))
      (node (ref "C40") (pin "1") (pinfunction "1_1") (pintype "passive"))
      (node (ref "C41") (pin "1") (pinfunction "1_1") (pintype "passive"))
      (node (ref "C42") (pin "1") (pinfunction "1_1") (pintype "passive"))
      (node (ref "C43") (pin "1") (pinfunction "1_1") (pintype "passive"))
      (node (ref "D1") (pin "C2") (pinfunction "C2_C2") (pintype "passive"))
      (node (ref "R11") (pin "2") (pinfunction "2_2") (pintype "passive"))
      (node (ref "U11") (pin "8") (pinfunction "V+_8") (pintype "passive"))
      (node (ref "U12") (pin "8") (pinfunction "V+_8") (pintype "passive"))
      (node (ref "U13") (pin "4") (pinfunction "VCC_4") (pintype "passive"))
      (node (ref "U14") (pin "1") (pinfunction "VDDIO_1") (pintype "passive"))
      (node (ref "U14") (pin "6") (pinfunction "VS_6") (pintype "passive"))
      (node (ref "U15") (pin "8") (pinfunction "VCC_8") (pintype "passive"))
      (node (ref "U16") (pin "1") (pinfunction "VDDIO_1") (pintype "passive"))
      (node (ref "U16") (pin "6") (pinfunction "VS_6") (pintype "passive"))
      (node (ref "U17") (pin "1") (pinfunction "VDDIO_1") (pintype "passive"))
      (node (ref "U17") (pin "6") (pinfunction "VS_6") (pintype "passive"))
      (node (ref "U18") (pin "8") (pinfunction "VCC_8") (pintype "passive"))
      (node (ref "U19") (pin "1") (pinfunction "VDDIO_1") (pintype "passive"))
      (node (ref "U19") (pin "6") (pinfunction "VS_6") (pintype "passive"))
      (node (ref "U2") (pin "3.3V1") (pinfunction "3.3V_3.3V1") (pintype "passive"))
      (node (ref "U2") (pin "3.3V2") (pinfunction "3.3V_3.3V2") (pintype "passive"))
      (node (ref "U5") (pin "5") (pinfunction "VCC_5") (pintype "passive"))
    )
    (net (code "6") (name "5V") (class "Default")
      (node (ref "C11") (pin "1") (pinfunction "1_1") (pintype "passive"))
      (node (ref "C12") (pin "1") (pinfunction "1_1") (pintype "passive"))
      (node (ref "C19") (pin "1") (pinfunction "1_1") (pintype "passive"))
      (node (ref "C2") (pin "1") (pinfunction "1_1") (pintype "passive"))
      (node (ref "C20") (pin "1") (pinfunction "1_1") (pintype "passive"))
      (node (ref "C21") (pin "1") (pinfunction "1_1") (pintype "passive"))
      (node (ref "C26") (pin "1") (pinfunction "1_1") (pintype "passive"))
      (node (ref "D10") (pin "1") (pinfunction "C_1") (pintype "passive"))
      (node (ref "D12") (pin "C2") (pinfunction "C2_C2") (pintype "passive"))
      (node (ref "D9") (pin "2") (pinfunction "A_2") (pintype "passive"))
      (node (ref "J1") (pin "2") (pinfunction "2_2") (pintype "passive"))
      (node (ref "J1") (pin "S1") (pinfunction "SHIELD_S1") (pintype "passive"))
      (node (ref "J1") (pin "S2") (pinfunction "SHIELD_S2") (pintype "passive"))
      (node (ref "R13") (pin "2") (pinfunction "2_2") (pintype "passive"))
      (node (ref "R6") (pin "2") (pinfunction "2_2") (pintype "passive"))
      (node (ref "U10") (pin "8") (pinfunction "V+_8") (pintype "passive"))
      (node (ref "U2") (pin "5V") (pinfunction "VIN_5V") (pintype "passive"))
      (node (ref "U3") (pin "5") (pinfunction "OUT_5") (pintype "passive"))
      (node (ref "U4") (pin "1") (pinfunction "IN_1") (pintype "passive"))
      (node (ref "U4") (pin "3") (pinfunction "EN_3") (pintype "passive"))
      (node (ref "U7") (pin "8") (pinfunction "V+_8") (pintype "passive"))
      (node (ref "U8") (pin "8") (pinfunction "V+_8") (pintype "passive"))
      (node (ref "U9") (pin "2") (pinfunction "V+_2") (pintype "passive"))
    )
    (net (code "7") (name "9V") (class "Default")
      (node (ref "C10") (pin "1") (pinfunction "1_1") (pintype "passive"))
      (node (ref "C17") (pin "1") (pinfunction "1_1") (pintype "passive"))
      (node (ref "C5") (pin "1") (pinfunction "1_1") (pintype "passive"))
      (node (ref "C6") (pin "1") (pinfunction "1_1") (pintype "passive"))
      (node (ref "C7") (pin "1") (pinfunction "1_1") (pintype "passive"))
      (node (ref "D15") (pin "1") (pinfunction "C_1") (pintype "passive"))
      (node (ref "D2") (pin "2") (pinfunction "A_2") (pintype "passive"))
      (node (ref "D6") (pin "C2") (pinfunction "C2_C2") (pintype "passive"))
      (node (ref "D9") (pin "1") (pinfunction "C_1") (pintype "passive"))
      (node (ref "J5") (pin "1") (pinfunction "1_1") (pintype "passive"))
      (node (ref "J6") (pin "1") (pinfunction "1_1") (pintype "passive"))
      (node (ref "L1") (pin "2") (pinfunction "2_2") (pintype "passive"))
      (node (ref "R3") (pin "1") (pinfunction "1_1") (pintype "passive"))
      (node (ref "R4") (pin "2") (pinfunction "2_2") (pintype "passive"))
      (node (ref "U3") (pin "1") (pinfunction "IN_1") (pintype "passive"))
      (node (ref "U3") (pin "3") (pinfunction "EN_3") (pintype "passive"))
      (node (ref "U6") (pin "4") (pinfunction "IN_4") (pintype "passive"))
      (node (ref "U6") (pin "6") (pinfunction "EN_6") (pintype "passive"))
    )
    (net (code "8") (name "10K_INT") (class "Default")
      (node (ref "R22") (pin "1") (pinfunction "1_1") (pintype "passive"))
      (node (ref "U11") (pin "7") (pinfunction "OUTA_7") (pintype "passive"))
      (node (ref "U2") (pin "23") (pinfunction "23/PWM/MCLK1/CRX1/A9_23") (pintype "passive"))
    )
    (net (code "9") (name "10K_OUT") (class "Default")
      (node (ref "R12") (pin "2") (pinfunction "2_2") (pintype "passive"))
      (node (ref "R18") (pin "1") (pinfunction "1_1") (pintype "passive"))
      (node (ref "U12") (pin "3") (pinfunction "INA+_3") (pintype "passive"))
      (node (ref "U7") (pin "1") (pinfunction "OUTA_1") (pintype "passive"))
    )
    (net (code "10") (name "10K_PEAK") (class "Default")
      (node (ref "C30") (pin "1") (pinfunction "1_1") (pintype "passive"))
      (node (ref "D16") (pin "1") (pinfunction "C_1") (pintype "passive"))
      (node (ref "R23") (pin "2") (pinfunction "2_2") (pintype "passive"))
      (node (ref "R24") (pin "2") (pinfunction "2_2") (pintype "passive"))
      (node (ref "U12") (pin "2") (pinfunction "INA-_2") (pintype "passive"))
      (node (ref "U2") (pin "20") (pinfunction "20/LRCLK1/TX5/A6_20") (pintype "passive"))
    )
    (net (code "11") (name "10K_REF") (class "Default")
      (node (ref "C8") (pin "1") (pinfunction "1_1") (pintype "passive"))
      (node (ref "R7") (pin "2") (pinfunction "2_2") (pintype "passive"))
      (node (ref "U11") (pin "2") (pinfunction "INA-_2") (pintype "passive"))
    )
    (net (code "12") (name "20K_INT") (class "Default")
      (node (ref "R32") (pin "1") (pinfunction "1_1") (pintype "passive"))
      (node (ref "U11") (pin "6") (pinfunction "OUTB_6") (pintype "passive"))
      (node (ref "U2") (pin "22") (pinfunction "22/PWM/CTX1/A8_22") (pintype "passive"))
    )
    (net (code "13") (name "20K_OUT") (class "Default")
      (node (ref "R21") (pin "2") (pinfunction "2_2") (pintype "passive"))
      (node (ref "R28") (pin "1") (pinfunction "1_1") (pintype "passive"))
      (node (ref "U10") (pin "1") (pinfunction "OUTA_1") (pintype "passive"))
      (node (ref "U12") (pin "5") (pinfunction "INB+_5") (pintype "passive"))
    )
    (net (code "14") (name "20K_PEAK") (class "Default")
      (node (ref "C32") (pin "1") (pinfunction "1_1") (pintype "passive"))
      (node (ref "D17") (pin "1") (pinfunction "C_1") (pintype "passive"))
      (node (ref "R25") (pin "2") (pinfunction "2_2") (pintype "passive"))
      (node (ref "R30") (pin "2") (pinfunction "2_2") (pintype "passive"))
      (node (ref "U12") (pin "6") (pinfunction "INB-_6") (pintype "passive"))
      (node (ref "U2") (pin "21") (pinfunction "21/BCLK1/RX5/A7_21") (pintype "passive"))
    )
    (net (code "15") (name "20K_REF") (class "Default")
      (node (ref "C9") (pin "1") (pinfunction "1_1") (pintype "passive"))
      (node (ref "R9") (pin "2") (pinfunction "2_2") (pintype "passive"))
      (node (ref "U11") (pin "4") (pinfunction "INB-_4") (pintype "passive"))
    )
    (net (code "16") (name "CS1") (class "Default")
      (node (ref "U14") (pin "7") (pinfunction "~{CS}_7") (pintype "passive"))
      (node (ref "U15") (pin "2") (pinfunction "B1_2") (pintype "passive"))
      (node (ref "U2") (pin "14") (pinfunction "14/PWM/SPDIF_OUT/TX3/A0_14") (pintype "passive"))
    )
    (net (code "17") (name "CS2") (class "Default")
      (node (ref "U15") (pin "6") (pinfunction "B2_6") (pintype "passive"))
      (node (ref "U16") (pin "7") (pinfunction "~{CS}_7") (pintype "passive"))
      (node (ref "U2") (pin "15") (pinfunction "15/PWM/SPDIF_IN/RX3/A1_15") (pintype "passive"))
    )
    (net (code "18") (name "CS3") (class "Default")
      (node (ref "U17") (pin "7") (pinfunction "~{CS}_7") (pintype "passive"))
      (node (ref "U18") (pin "2") (pinfunction "B1_2") (pintype "passive"))
      (node (ref "U2") (pin "10") (pinfunction "10/PWM/MQSR/CS_10") (pintype "passive"))
    )
    (net (code "19") (name "CS4") (class "Default")
      (node (ref "U18") (pin "6") (pinfunction "B2_6") (pintype "passive"))
      (node (ref "U19") (pin "7") (pinfunction "~{CS}_7") (pintype "passive"))
      (node (ref "U2") (pin "24") (pinfunction "24/PWM/SCL2/TX6/A10_24") (pintype "passive"))
    )
    (net (code "20") (name "ESC_L") (class "Default")
      (node (ref "J3") (pin "1") (pinfunction "1_1") (pintype "passive"))
      (node (ref "U2") (pin "28") (pinfunction "28/PWM/RX7_28") (pintype "passive"))
    )
    (net (code "21") (name "ESC_R") (class "Default")
      (node (ref "J3") (pin "2") (pinfunction "2_2") (pintype "passive"))
      (node (ref "U2") (pin "29") (pinfunction "29/PWM/TX7_29") (pintype "passive"))
    )
    (net (code "22") (name "GND") (class "Default")
      (node (ref "C1") (pin "2") (pinfunction "2_2") (pintype "passive"))
      (node (ref "C10") (pin "2") (pinfunction "2_2") (pintype "passive"))
      (node (ref "C11") (pin "2") (pinfunction "2_2") (pintype "passive"))
      (node (ref "C12") (pin "2") (pinfunction "2_2") (pintype "passive"))
      (node (ref "C13") (pin "2") (pinfunction "2_2") (pintype "passive"))
      (node (ref "C14") (pin "2") (pinfunction "2_2") (pintype "passive"))
      (node (ref "C15") (pin "2") (pinfunction "2_2") (pintype "passive"))
      (node (ref "C16") (pin "2") (pinfunction "2_2") (pintype "passive"))
      (node (ref "C17") (pin "2") (pinfunction "2_2") (pintype "passive"))
      (node (ref "C18") (pin "2") (pinfunction "2_2") (pintype "passive"))
      (node (ref "C19") (pin "2") (pinfunction "2_2") (pintype "passive"))
      (node (ref "C2") (pin "2") (pinfunction "2_2") (pintype "passive"))
      (node (ref "C20") (pin "2") (pinfunction "2_2") (pintype "passive"))
      (node (ref "C21") (pin "2") (pinfunction "2_2") (pintype "passive"))
      (node (ref "C26") (pin "2") (pinfunction "2_2") (pintype "passive"))
      (node (ref "C27") (pin "2") (pinfunction "2_2") (pintype "passive"))
      (node (ref "C28") (pin "2") (pinfunction "2_2") (pintype "passive"))
      (node (ref "C30") (pin "2") (pinfunction "2_2") (pintype "passive"))
      (node (ref "C32") (pin "2") (pinfunction "2_2") (pintype "passive"))
      (node (ref "C33") (pin "2") (pinfunction "2_2") (pintype "passive"))
      (node (ref "C34") (pin "2") (pinfunction "2_2") (pintype "passive"))
      (node (ref "C35") (pin "2") (pinfunction "2_2") (pintype "passive"))
      (node (ref "C36") (pin "2") (pinfunction "2_2") (pintype "passive"))
      (node (ref "C37") (pin "2") (pinfunction "2_2") (pintype "passive"))
      (node (ref "C38") (pin "2") (pinfunction "2_2") (pintype "passive"))
      (node (ref "C39") (pin "2") (pinfunction "2_2") (pintype "passive"))
      (node (ref "C4") (pin "2") (pinfunction "2_2") (pintype "passive"))
      (node (ref "C40") (pin "2") (pinfunction "2_2") (pintype "passive"))
      (node (ref "C41") (pin "2") (pinfunction "2_2") (pintype "passive"))
      (node (ref "C42") (pin "2") (pinfunction "2_2") (pintype "passive"))
      (node (ref "C43") (pin "2") (pinfunction "2_2") (pintype "passive"))
      (node (ref "C46") (pin "2") (pinfunction "2_2") (pintype "passive"))
      (node (ref "C47") (pin "2") (pinfunction "2_2") (pintype "passive"))
      (node (ref "C48") (pin "2") (pinfunction "2_2") (pintype "passive"))
      (node (ref "C49") (pin "2") (pinfunction "2_2") (pintype "passive"))
      (node (ref "C50") (pin "2") (pinfunction "2_2") (pintype "passive"))
      (node (ref "C53") (pin "2") (pinfunction "2_2") (pintype "passive"))
      (node (ref "C55") (pin "2") (pinfunction "2_2") (pintype "passive"))
      (node (ref "C6") (pin "2") (pinfunction "2_2") (pintype "passive"))
      (node (ref "C7") (pin "2") (pinfunction "2_2") (pintype "passive"))
      (node (ref "C8") (pin "2") (pinfunction "2_2") (pintype "passive"))
      (node (ref "C9") (pin "2") (pinfunction "2_2") (pintype "passive"))
      (node (ref "CN1") (pin "2") (pinfunction "2_2") (pintype "passive"))
      (node (ref "D1") (pin "C1") (pinfunction "C1_C1") (pintype "passive"))
      (node (ref "D11") (pin "C") (pinfunction "C_C") (pintype "passive"))
      (node (ref "D12") (pin "C1") (pinfunction "C1_C1") (pintype "passive"))
      (node (ref "D13") (pin "C1") (pinfunction "C1_C1") (pintype "passive"))
      (node (ref "D14") (pin "C") (pinfunction "C_C") (pintype "passive"))
      (node (ref "D3") (pin "C") (pinfunction "C_C") (pintype "passive"))
      (node (ref "D4") (pin "2") (pinfunction "A_2") (pintype "passive"))
      (node (ref "D5") (pin "C") (pinfunction "C_C") (pintype "passive"))
      (node (ref "D6") (pin "C1") (pinfunction "C1_C1") (pintype "passive"))
      (node (ref "D7") (pin "C") (pinfunction "C_C") (pintype "passive"))
      (node (ref "D8") (pin "C") (pinfunction "C_C") (pintype "passive"))
      (node (ref "J1") (pin "3") (pinfunction "3_3") (pintype "passive"))
      (node (ref "J2") (pin "4") (pinfunction "4_4") (pintype "passive"))
      (node (ref "J3") (pin "S1") (pinfunction "SHIELD_S1") (pintype "passive"))
      (node (ref "J3") (pin "S2") (pinfunction "SHIELD_S2") (pintype "passive"))
      (node (ref "J4") (pin "4") (pinfunction "4_4") (pintype "passive"))
      (node (ref "J5") (pin "3") (pinfunction "3_3") (pintype "passive"))
      (node (ref "J5") (pin "S1") (pinfunction "SHIELD_S1") (pintype "passive"))
      (node (ref "J5") (pin "S2") (pinfunction "SHIELD_S2") (pintype "passive"))
      (node (ref "J6") (pin "3") (pinfunction "3_3") (pintype "passive"))
      (node (ref "J6") (pin "S1") (pinfunction "SHIELD_S1") (pintype "passive"))
      (node (ref "J6") (pin "S2") (pinfunction "SHIELD_S2") (pintype "passive"))
      (node (ref "R14") (pin "1") (pinfunction "1_1") (pintype "passive"))
      (node (ref "R15") (pin "1") (pinfunction "1_1") (pintype "passive"))
      (node (ref "R24") (pin "1") (pinfunction "1_1") (pintype "passive"))
      (node (ref "R30") (pin "1") (pinfunction "1_1") (pintype "passive"))
      (node (ref "R47") (pin "2") (pinfunction "2_2") (pintype "passive"))
      (node (ref "R48") (pin "2") (pinfunction "2_2") (pintype "passive"))
      (node (ref "R5") (pin "2") (pinfunction "2_2") (pintype "passive"))
      (node (ref "U1") (pin "4") (pinfunction "GND_4") (pintype "passive"))
      (node (ref "U10") (pin "4") (pinfunction "V-_4") (pintype "passive"))
      (node (ref "U11") (pin "5") (pinfunction "V-_5") (pintype "passive"))
      (node (ref "U12") (pin "4") (pinfunction "V-_4") (pintype "passive"))
      (node (ref "U13") (pin "2") (pinfunction "GND_2") (pintype "passive"))
      (node (ref "U14") (pin "2") (pinfunction "GND_2") (pintype "passive"))
      (node (ref "U14") (pin "4") (pinfunction "GND_4") (pintype "passive"))
      (node (ref "U14") (pin "5") (pinfunction "GND_5") (pintype "passive"))
      (node (ref "U15") (pin "4") (pinfunction "GND_4") (pintype "passive"))
      (node (ref "U16") (pin "2") (pinfunction "GND_2") (pintype "passive"))
      (node (ref "U16") (pin "4") (pinfunction "GND_4") (pintype "passive"))
      (node (ref "U16") (pin "5") (pinfunction "GND_5") (pintype "passive"))
      (node (ref "U17") (pin "2") (pinfunction "GND_2") (pintype "passive"))
      (node (ref "U17") (pin "4") (pinfunction "GND_4") (pintype "passive"))
      (node (ref "U17") (pin "5") (pinfunction "GND_5") (pintype "passive"))
      (node (ref "U18") (pin "4") (pinfunction "GND_4") (pintype "passive"))
      (node (ref "U19") (pin "2") (pinfunction "GND_2") (pintype "passive"))
      (node (ref "U19") (pin "4") (pinfunction "GND_4") (pintype "passive"))
      (node (ref "U19") (pin "5") (pinfunction "GND_5") (pintype "passive"))
      (node (ref "U2") (pin "GND1") (pinfunction "GND_GND1") (pintype "passive"))
      (node (ref "U2") (pin "GND2") (pinfunction "GND_GND2") (pintype "passive"))
      (node (ref "U2") (pin "GND3") (pinfunction "GND_GND3") (pintype "passive"))
      (node (ref "U20") (pin "4") (pinfunction "V-_4") (pintype "passive"))
      (node (ref "U21") (pin "4") (pinfunction "V-_4") (pintype "passive"))
      (node (ref "U22") (pin "1") (pinfunction "GND2(A)_1") (pintype "passive"))
      (node (ref "U22") (pin "11") (pinfunction "S/R-_11") (pintype "passive"))
      (node (ref "U22") (pin "13") (pinfunction "GND1(A)_13") (pintype "passive"))
      (node (ref "U22") (pin "15") (pinfunction "GND1(B)_15") (pintype "passive"))
      (node (ref "U22") (pin "6") (pinfunction "OFF-_6") (pintype "passive"))
      (node (ref "U22") (pin "7") (pinfunction "GND2(B)_7") (pintype "passive"))
      (node (ref "U23") (pin "4") (pinfunction "V-_4") (pintype "passive"))
      (node (ref "U23") (pin "5") (pinfunction "INB+_5") (pintype "passive"))
      (node (ref "U23") (pin "6") (pinfunction "INB-_6") (pintype "passive"))
      (node (ref "U24") (pin "1") (pinfunction "S1_1") (pintype "passive"))
      (node (ref "U3") (pin "2") (pinfunction "GND_2") (pintype "passive"))
      (node (ref "U4") (pin "2") (pinfunction "GND_2") (pintype "passive"))
      (node (ref "U5") (pin "3") (pinfunction "GND_3") (pintype "bidirectional"))
      (node (ref "U6") (pin "1") (pinfunction "GND_1") (pintype "passive"))
      (node (ref "U6") (pin "7") (pinfunction "GND_7") (pintype "passive"))
      (node (ref "U7") (pin "4") (pinfunction "V-_4") (pintype "passive"))
      (node (ref "U8") (pin "4") (pinfunction "V-_4") (pintype "passive"))
      (node (ref "U9") (pin "3") (pinfunction "GND_3") (pintype "passive"))
    )
    (net (code "23") (name "IR_BOTTOM") (class "Default")
      (node (ref "J6") (pin "2") (pinfunction "2_2") (pintype "passive"))
      (node (ref "U9") (pin "6") (pinfunction "S2_6") (pintype "passive"))
    )
    (net (code "24") (name "IR_SEL") (class "Default")
      (node (ref "U2") (pin "37") (pinfunction "37/PWM/CS_37") (pintype "passive"))
      (node (ref "U9") (pin "1") (pinfunction "SEL_1") (pintype "passive"))
    )
    (net (code "25") (name "IR_TOP") (class "Default")
      (node (ref "J5") (pin "2") (pinfunction "2_2") (pintype "passive"))
      (node (ref "U9") (pin "4") (pinfunction "S1_4") (pintype "passive"))
    )
    (net (code "26") (name "LED_CLK1") (class "Default")
      (node (ref "J2") (pin "2") (pinfunction "2_2") (pintype "passive"))
      (node (ref "U2") (pin "2") (pinfunction "2/PWM/OUT2_2") (pintype "passive"))
    )
    (net (code "27") (name "LED_CLK2") (class "Default")
      (node (ref "J4") (pin "2") (pinfunction "2_2") (pintype "passive"))
      (node (ref "U2") (pin "4") (pinfunction "4/PWM/BCLK2_4") (pintype "passive"))
    )
    (net (code "28") (name "LED_DATA1") (class "Default")
      (node (ref "J2") (pin "3") (pinfunction "3_3") (pintype "passive"))
      (node (ref "U2") (pin "1") (pinfunction "1/PWM/CTX2/MISO1/TX1_1") (pintype "passive"))
    )
    (net (code "29") (name "LED_DATA2") (class "Default")
      (node (ref "J4") (pin "3") (pinfunction "3_3") (pintype "passive"))
      (node (ref "U2") (pin "3") (pinfunction "3/PWM/LRCLK2_3") (pintype "passive"))
    )
    (net (code "30") (name "MAG_FILT_A") (class "Default")
      (node (ref "C45") (pin "2") (pinfunction "2_2") (pintype "passive"))
      (node (ref "U2") (pin "38") (pinfunction "38/IN1/CS1/A14_38") (pintype "passive"))
      (node (ref "U21") (pin "1") (pinfunction "OUTA_1") (pintype "passive"))
      (node (ref "U21") (pin "2") (pinfunction "INA-_2") (pintype "passive"))
    )
    (net (code "31") (name "MAG_FILT_B") (class "Default")
      (node (ref "C51") (pin "2") (pinfunction "2_2") (pintype "passive"))
      (node (ref "U2") (pin "39") (pinfunction "39/OUT1A/MISO1/A15_39") (pintype "passive"))
      (node (ref "U21") (pin "6") (pinfunction "INB-_6") (pintype "passive"))
      (node (ref "U21") (pin "7") (pinfunction "OUTB_7") (pintype "passive"))
    )
    (net (code "32") (name "MISO") (class "Default")
      (node (ref "U14") (pin "12") (pinfunction "SDO/ALT_12") (pintype "passive"))
      (node (ref "U16") (pin "12") (pinfunction "SDO/ALT_12") (pintype "passive"))
      (node (ref "U17") (pin "12") (pinfunction "SDO/ALT_12") (pintype "passive"))
      (node (ref "U19") (pin "12") (pinfunction "SDO/ALT_12") (pintype "passive"))
      (node (ref "U2") (pin "12") (pinfunction "12/PWM/MQSL/MISO_12") (pintype "passive"))
    )
    (net (code "33") (name "MOSI") (class "Default")
      (node (ref "U15") (pin "1") (pinfunction "A1_1") (pintype "passive"))
      (node (ref "U15") (pin "5") (pinfunction "A2_5") (pintype "passive"))
      (node (ref "U18") (pin "1") (pinfunction "A1_1") (pintype "passive"))
      (node (ref "U18") (pin "5") (pinfunction "A2_5") (pintype "passive"))
      (node (ref "U2") (pin "11") (pinfunction "11/PWM/CTX1/MOSI_11") (pintype "passive"))
    )
    (net (code "34") (name "MOSI1") (class "Default")
      (node (ref "U14") (pin "13") (pinfunction "SDI/SDA_13") (pintype "passive"))
      (node (ref "U15") (pin "7") (pinfunction "Y1_7") (pintype "passive"))
    )
    (net (code "35") (name "MOSI2") (class "Default")
      (node (ref "U15") (pin "3") (pinfunction "Y2_3") (pintype "passive"))
      (node (ref "U16") (pin "13") (pinfunction "SDI/SDA_13") (pintype "passive"))
    )
    (net (code "36") (name "MOSI3") (class "Default")
      (node (ref "U17") (pin "13") (pinfunction "SDI/SDA_13") (pintype "passive"))
      (node (ref "U18") (pin "7") (pinfunction "Y1_7") (pintype "passive"))
    )
    (net (code "37") (name "MOSI4") (class "Default")
      (node (ref "U18") (pin "3") (pinfunction "Y2_3") (pintype "passive"))
      (node (ref "U19") (pin "13") (pinfunction "SDI/SDA_13") (pintype "passive"))
    )
    (net (code "38") (name "Net-(C45-Pad1)") (class "Default")
      (node (ref "C45") (pin "1") (pinfunction "1_1") (pintype "passive"))
      (node (ref "R34") (pin "1") (pinfunction "1_1") (pintype "passive"))
      (node (ref "R35") (pin "2") (pinfunction "2_2") (pintype "passive"))
    )
    (net (code "39") (name "Net-(C51-Pad1)") (class "Default")
      (node (ref "C51") (pin "1") (pinfunction "1_1") (pintype "passive"))
      (node (ref "R39") (pin "1") (pinfunction "1_1") (pintype "passive"))
      (node (ref "R40") (pin "2") (pinfunction "2_2") (pintype "passive"))
    )
    (net (code "40") (name "Net-(C54-Pad1)") (class "Default")
      (node (ref "C54") (pin "1") (pinfunction "1_1") (pintype "passive"))
      (node (ref "U24") (pin "5") (pinfunction "D2_5") (pintype "passive"))
      (node (ref "U24") (pin "6") (pinfunction "D2_6") (pintype "passive"))
      (node (ref "U24") (pin "7") (pinfunction "D1_7") (pintype "passive"))
      (node (ref "U24") (pin "8") (pinfunction "D1_8") (pintype "passive"))
    )
    (net (code "41") (name "Net-(D3-PadA)") (class "Default")
      (node (ref "D3") (pin "A") (pinfunction "A_A") (pintype "passive"))
      (node (ref "R2") (pin "1") (pinfunction "1_1") (pintype "passive"))
    )
    (net (code "42") (name "Net-(D5-PadA)") (class "Default")
      (node (ref "D5") (pin "A") (pinfunction "A_A") (pintype "passive"))
      (node (ref "R4") (pin "1") (pinfunction "1_1") (pintype "passive"))
    )
    (net (code "43") (name "Net-(D7-PadA)") (class "Default")
      (node (ref "D7") (pin "A") (pinfunction "A_A") (pintype "passive"))
      (node (ref "R6") (pin "1") (pinfunction "1_1") (pintype "passive"))
    )
    (net (code "44") (name "Net-(D8-PadA)") (class "Default")
      (node (ref "D8") (pin "A") (pinfunction "A_A") (pintype "passive"))
      (node (ref "R8") (pin "1") (pinfunction "1_1") (pintype "passive"))
    )
    (net (code "45") (name "Net-(D11-PadA)") (class "Default")
      (node (ref "D11") (pin "A") (pinfunction "A_A") (pintype "passive"))
      (node (ref "R10") (pin "1") (pinfunction "1_1") (pintype "passive"))
    )
    (net (code "46") (name "Net-(D14-PadA)") (class "Default")
      (node (ref "D14") (pin "A") (pinfunction "A_A") (pintype "passive"))
      (node (ref "R11") (pin "1") (pinfunction "1_1") (pintype "passive"))
    )
    (net (code "47") (name "Net-(D16-A)") (class "Default")
      (node (ref "D16") (pin "2") (pinfunction "A_2") (pintype "passive"))
      (node (ref "U12") (pin "1") (pinfunction "OUTA_1") (pintype "passive"))
    )
    (net (code "48") (name "Net-(D17-A)") (class "Default")
      (node (ref "D17") (pin "2") (pinfunction "A_2") (pintype "passive"))
      (node (ref "U12") (pin "7") (pinfunction "OUTB_7") (pintype "passive"))
    )
    (net (code "49") (name "Net-(R1-Pad1)") (class "Default")
      (node (ref "R1") (pin "1") (pinfunction "1_1") (pintype "passive"))
      (node (ref "R2") (pin "2") (pinfunction "2_2") (pintype "passive"))
    )
    (net (code "50") (name "Net-(U1-BST)") (class "Default")
      (node (ref "C3") (pin "1") (pinfunction "1_1") (pintype "passive"))
      (node (ref "U1") (pin "6") (pinfunction "BST_6") (pintype "passive"))
    )
    (net (code "51") (name "Net-(U1-FB)") (class "Default")
      (node (ref "C5") (pin "2") (pinfunction "2_2") (pintype "passive"))
      (node (ref "R3") (pin "2") (pinfunction "2_2") (pintype "passive"))
      (node (ref "R5") (pin "1") (pinfunction "1_1") (pintype "passive"))
      (node (ref "U1") (pin "1") (pinfunction "FB_1") (pintype "bidirectional"))
    )
    (net (code "52") (name "Net-(U1-SW)") (class "Default")
      (node (ref "C3") (pin "2") (pinfunction "2_2") (pintype "passive"))
      (node (ref "L1") (pin "1") (pinfunction "1_1") (pintype "passive"))
      (node (ref "U1") (pin "5") (pinfunction "SW_5") (pintype "bidirectional"))
    )
    (net (code "53") (name "Net-(U2-18{slash}PWM{slash}SDA{slash}A4)") (class "Default")
      (node (ref "R7") (pin "1") (pinfunction "1_1") (pintype "passive"))
      (node (ref "U2") (pin "18") (pinfunction "18/PWM/SDA/A4_18") (pintype "passive"))
    )
    (net (code "54") (name "Net-(U2-19{slash}PWM{slash}SCL{slash}A5)") (class "Default")
      (node (ref "R9") (pin "1") (pinfunction "1_1") (pintype "passive"))
      (node (ref "U2") (pin "19") (pinfunction "19/PWM/SCL/A5_19") (pintype "passive"))
    )
    (net (code "55") (name "Net-(U3-BYP)") (class "Default")
      (node (ref "C14") (pin "1") (pinfunction "1_1") (pintype "passive"))
      (node (ref "U3") (pin "4") (pinfunction "BYP_4") (pintype "bidirectional"))
    )
    (net (code "56") (name "Net-(U4-BYP)") (class "Default")
      (node (ref "C15") (pin "1") (pinfunction "1_1") (pintype "passive"))
      (node (ref "U4") (pin "4") (pinfunction "BYP_4") (pintype "bidirectional"))
    )
    (net (code "57") (name "Net-(U7-INA+)") (class "Default")
      (node (ref "C24") (pin "1") (pinfunction "1_1") (pintype "passive"))
      (node (ref "C25") (pin "1") (pinfunction "1_1") (pintype "passive"))
      (node (ref "R16") (pin "1") (pinfunction "1_1") (pintype "passive"))
      (node (ref "R17") (pin "1") (pinfunction "1_1") (pintype "passive"))
      (node (ref "R19") (pin "2") (pinfunction "2_2") (pintype "passive"))
      (node (ref "U7") (pin "3") (pinfunction "INA+_3") (pintype "passive"))
    )
    (net (code "58") (name "Net-(U7-INA-)") (class "Default")
      (node (ref "C22") (pin "1") (pinfunction "1_1") (pintype "passive"))
      (node (ref "C23") (pin "1") (pinfunction "1_1") (pintype "passive"))
      (node (ref "R12") (pin "1") (pinfunction "1_1") (pintype "passive"))
      (node (ref "U7") (pin "2") (pinfunction "INA-_2") (pintype "passive"))
      (node (ref "U7") (pin "6") (pinfunction "INB-_6") (pintype "passive"))
    )
    (net (code "59") (name "Net-(U7-INB+)") (class "Default")
      (node (ref "R18") (pin "2") (pinfunction "2_2") (pintype "passive"))
      (node (ref "R20") (pin "2") (pinfunction "2_2") (pintype "passive"))
      (node (ref "U7") (pin "5") (pinfunction "INB+_5") (pintype "passive"))
    )
    (net (code "60") (name "Net-(U7-OUTB)") (class "Default")
      (node (ref "C22") (pin "2") (pinfunction "2_2") (pintype "passive"))
      (node (ref "C23") (pin "2") (pinfunction "2_2") (pintype "passive"))
      (node (ref "R17") (pin "2") (pinfunction "2_2") (pintype "passive"))
      (node (ref "U7") (pin "7") (pinfunction "OUTB_7") (pintype "passive"))
    )
    (net (code "61") (name "Net-(U8-INB+)") (class "Default")
      (node (ref "R13") (pin "1") (pinfunction "1_1") (pintype "passive"))
      (node (ref "R15") (pin "2") (pinfunction "2_2") (pintype "passive"))
      (node (ref "U8") (pin "5") (pinfunction "INB+_5") (pintype "passive"))
    )
    (net (code "62") (name "Net-(U10-INA+)") (class "Default")
      (node (ref "C31") (pin "1") (pinfunction "1_1") (pintype "passive"))
      (node (ref "R26") (pin "1") (pinfunction "1_1") (pintype "passive"))
      (node (ref "R27") (pin "1") (pinfunction "1_1") (pintype "passive"))
      (node (ref "R29") (pin "2") (pinfunction "2_2") (pintype "passive"))
      (node (ref "U10") (pin "3") (pinfunction "INA+_3") (pintype "passive"))
    )
    (net (code "63") (name "Net-(U10-INA-)") (class "Default")
      (node (ref "C29") (pin "1") (pinfunction "1_1") (pintype "passive"))
      (node (ref "R21") (pin "1") (pinfunction "1_1") (pintype "passive"))
      (node (ref "U10") (pin "2") (pinfunction "INA-_2") (pintype "passive"))
      (node (ref "U10") (pin "6") (pinfunction "INB-_6") (pintype "passive"))
    )
    (net (code "64") (name "Net-(U10-INB+)") (class "Default")
      (node (ref "R28") (pin "2") (pinfunction "2_2") (pintype "passive"))
      (node (ref "R31") (pin "2") (pinfunction "2_2") (pintype "passive"))
      (node (ref "U10") (pin "5") (pinfunction "INB+_5") (pintype "passive"))
    )
    (net (code "65") (name "Net-(U10-OUTB)") (class "Default")
      (node (ref "C29") (pin "2") (pinfunction "2_2") (pintype "passive"))
      (node (ref "R27") (pin "2") (pinfunction "2_2") (pintype "passive"))
      (node (ref "U10") (pin "7") (pinfunction "OUTB_7") (pintype "passive"))
    )
    (net (code "66") (name "Net-(U11-INA+)") (class "Default")
      (node (ref "R22") (pin "2") (pinfunction "2_2") (pintype "passive"))
      (node (ref "R23") (pin "1") (pinfunction "1_1") (pintype "passive"))
      (node (ref "U11") (pin "1") (pinfunction "INA+_1") (pintype "passive"))
    )
    (net (code "67") (name "Net-(U11-INB+)") (class "Default")
      (node (ref "R25") (pin "1") (pinfunction "1_1") (pintype "passive"))
      (node (ref "R32") (pin "2") (pinfunction "2_2") (pintype "passive"))
      (node (ref "U11") (pin "3") (pinfunction "INB+_3") (pintype "passive"))
    )
    (net (code "68") (name "Net-(U20-INA+)") (class "Default")
      (node (ref "C44") (pin "1") (pinfunction "1_1") (pintype "passive"))
      (node (ref "R33") (pin "2") (pinfunction "2_2") (pintype "passive"))
      (node (ref "R36") (pin "1") (pinfunction "1_1") (pintype "passive"))
      (node (ref "U20") (pin "3") (pinfunction "INA+_3") (pintype "passive"))
    )
    (net (code "69") (name "Net-(U20-INA-)") (class "Default")
      (node (ref "R37") (pin "1") (pinfunction "1_1") (pintype "passive"))
      (node (ref "R42") (pin "1") (pinfunction "1_1") (pintype "passive"))
      (node (ref "U20") (pin "2") (pinfunction "INA-_2") (pintype "passive"))
    )
    (net (code "70") (name "Net-(U20-INB+)") (class "Default")
      (node (ref "C52") (pin "1") (pinfunction "1_1") (pintype "passive"))
      (node (ref "R38") (pin "1") (pinfunction "1_1") (pintype "passive"))
      (node (ref "R44") (pin "2") (pinfunction "2_2") (pintype "passive"))
      (node (ref "U20") (pin "5") (pinfunction "INB+_5") (pintype "passive"))
    )
    (net (code "71") (name "Net-(U20-INB-)") (class "Default")
      (node (ref "R41") (pin "1") (pinfunction "1_1") (pintype "passive"))
      (node (ref "R43") (pin "1") (pinfunction "1_1") (pintype "passive"))
      (node (ref "U20") (pin "6") (pinfunction "INB-_6") (pintype "passive"))
    )
    (net (code "72") (name "Net-(U20-OUTA)") (class "Default")
      (node (ref "C44") (pin "2") (pinfunction "2_2") (pintype "passive"))
      (node (ref "R33") (pin "1") (pinfunction "1_1") (pintype "passive"))
      (node (ref "R34") (pin "2") (pinfunction "2_2") (pintype "passive"))
      (node (ref "U20") (pin "1") (pinfunction "OUTA_1") (pintype "passive"))
    )
    (net (code "73") (name "Net-(U20-OUTB)") (class "Default")
      (node (ref "C52") (pin "2") (pinfunction "2_2") (pintype "passive"))
      (node (ref "R39") (pin "2") (pinfunction "2_2") (pintype "passive"))
      (node (ref "R44") (pin "1") (pinfunction "1_1") (pintype "passive"))
      (node (ref "U20") (pin "7") (pinfunction "OUTB_7") (pintype "passive"))
    )
    (net (code "74") (name "Net-(U21-INA+)") (class "Default")
      (node (ref "C48") (pin "1") (pinfunction "1_1") (pintype "passive"))
      (node (ref "R35") (pin "1") (pinfunction "1_1") (pintype "passive"))
      (node (ref "U21") (pin "3") (pinfunction "INA+_3") (pintype "passive"))
    )
    (net (code "75") (name "Net-(U21-INB+)") (class "Default")
      (node (ref "C50") (pin "1") (pinfunction "1_1") (pintype "passive"))
      (node (ref "R40") (pin "1") (pinfunction "1_1") (pintype "passive"))
      (node (ref "U21") (pin "5") (pinfunction "INB+_5") (pintype "passive"))
    )
    (net (code "76") (name "Net-(U22-OUT+(A))") (class "Default")
      (node (ref "R36") (pin "2") (pinfunction "2_2") (pintype "passive"))
      (node (ref "U22") (pin "3") (pinfunction "OUT+(A)_3") (pintype "passive"))
    )
    (net (code "77") (name "Net-(U22-OUT+(B))") (class "Default")
      (node (ref "R38") (pin "2") (pinfunction "2_2") (pintype "passive"))
      (node (ref "U22") (pin "16") (pinfunction "OUT+(B)_16") (pintype "passive"))
    )
    (net (code "78") (name "Net-(U22-OUT-(A))") (class "Default")
      (node (ref "R37") (pin "2") (pinfunction "2_2") (pintype "passive"))
      (node (ref "U22") (pin "14") (pinfunction "OUT-(A)_14") (pintype "passive"))
    )
    (net (code "79") (name "Net-(U22-OUT-(B))") (class "Default")
      (node (ref "R41") (pin "2") (pinfunction "2_2") (pintype "passive"))
      (node (ref "U22") (pin "10") (pinfunction "OUT-(B)_10") (pintype "passive"))
    )
    (net (code "80") (name "Net-(U23-INA+)") (class "Default")
      (node (ref "R45") (pin "2") (pinfunction "2_2") (pintype "passive"))
      (node (ref "R47") (pin "1") (pinfunction "1_1") (pintype "passive"))
      (node (ref "U23") (pin "3") (pinfunction "INA+_3") (pintype "passive"))
    )
    (net (code "81") (name "Net-(U23-OUTB)") (class "Default")
      (node (ref "R48") (pin "1") (pinfunction "1_1") (pintype "passive"))
      (node (ref "U23") (pin "7") (pinfunction "OUTB_7") (pintype "passive"))
    )
    (net (code "82") (name "Net-(U24-S2)") (class "Default")
      (node (ref "C55") (pin "1") (pinfunction "1_1") (pintype "passive"))
      (node (ref "R46") (pin "2") (pinfunction "2_2") (pintype "passive"))
      (node (ref "U24") (pin "3") (pinfunction "S2_3") (pintype "passive"))
    )
    (net (code "83") (name "RC_SIGNAL") (class "Default")
      (node (ref "J1") (pin "1") (pinfunction "1_1") (pintype "passive"))
      (node (ref "U5") (pin "2") (pinfunction "IN_2") (pintype "passive"))
    )
    (net (code "84") (name "SBUS") (class "Default")
      (node (ref "U2") (pin "0") (pinfunction "0/PWM/CRX2/CS1/RX1_0") (pintype "passive"))
      (node (ref "U5") (pin "4") (pinfunction "OUT_4") (pintype "passive"))
    )
    (net (code "85") (name "SCLK") (class "Default")
      (node (ref "U14") (pin "14") (pinfunction "SCLK/SCL_14") (pintype "passive"))
      (node (ref "U16") (pin "14") (pinfunction "SCLK/SCL_14") (pintype "passive"))
      (node (ref "U17") (pin "14") (pinfunction "SCLK/SCL_14") (pintype "passive"))
      (node (ref "U19") (pin "14") (pinfunction "SCLK/SCL_14") (pintype "passive"))
      (node (ref "U2") (pin "13") (pinfunction "13/(LED)/SCK_13") (pintype "passive"))
    )
    (net (code "86") (name "S{slash}R") (class "Default")
      (node (ref "U2") (pin "32") (pinfunction "32/OUT1B_32") (pintype "passive"))
      (node (ref "U24") (pin "2") (pinfunction "G1_2") (pintype "passive"))
      (node (ref "U24") (pin "4") (pinfunction "G2_4") (pintype "passive"))
    )
    (net (code "87") (name "S{slash}R+") (class "Default")
      (node (ref "C54") (pin "2") (pinfunction "2_2") (pintype "passive"))
      (node (ref "U22") (pin "8") (pinfunction "S/R+_8") (pintype "passive"))
    )
    (net (code "88") (name "TEMP") (class "Default")
      (node (ref "U13") (pin "3") (pinfunction "VOUT_3") (pintype "passive"))
      (node (ref "U2") (pin "26") (pinfunction "26/MOSI1/A12_26") (pintype "passive"))
    )
    (net (code "89") (name "VG_SIGNAL") (class "Default")
      (node (ref "R14") (pin "2") (pinfunction "2_2") (pintype "passive"))
      (node (ref "U8") (pin "3") (pinfunction "INA+_3") (pintype "passive"))
      (node (ref "U9") (pin "5") (pinfunction "D_5") (pintype "passive"))
    )
    (net (code "90") (name "VG_SIGNAL_BUF") (class "Default")
      (node (ref "R16") (pin "2") (pinfunction "2_2") (pintype "passive"))
      (node (ref "R26") (pin "2") (pinfunction "2_2") (pintype "passive"))
      (node (ref "U8") (pin "1") (pinfunction "OUTA_1") (pintype "passive"))
      (node (ref "U8") (pin "2") (pinfunction "INA-_2") (pintype "passive"))
    )
    (net (code "91") (name "VREF{slash}2") (class "Default")
      (node (ref "R42") (pin "2") (pinfunction "2_2") (pintype "passive"))
      (node (ref "R43") (pin "2") (pinfunction "2_2") (pintype "passive"))
      (node (ref "U23") (pin "1") (pinfunction "OUTA_1") (pintype "passive"))
      (node (ref "U23") (pin "2") (pinfunction "INA-_2") (pintype "passive"))
    )
    (net (code "92") (name "unconnected-(U2-5{slash}IN2-Pad5)") (class "Default")
      (node (ref "U2") (pin "5") (pinfunction "5/IN2_5") (pintype "passive"))
    )
    (net (code "93") (name "unconnected-(U2-6{slash}PWM{slash}OUT1D-Pad6)") (class "Default")
      (node (ref "U2") (pin "6") (pinfunction "6/PWM/OUT1D_6") (pintype "passive"))
    )
    (net (code "94") (name "unconnected-(U2-7{slash}PWM{slash}OUT1A{slash}RX2-Pad7)") (class "Default")
      (node (ref "U2") (pin "7") (pinfunction "7/PWM/OUT1A/RX2_7") (pintype "passive"))
    )
    (net (code "95") (name "unconnected-(U2-8{slash}PWM{slash}IN1{slash}TX2-Pad8)") (class "Default")
      (node (ref "U2") (pin "8") (pinfunction "8/PWM/IN1/TX2_8") (pintype "passive"))
    )
    (net (code "96") (name "unconnected-(U2-9{slash}PWM{slash}OUT1C-Pad9)") (class "Default")
      (node (ref "U2") (pin "9") (pinfunction "9/PWM/OUT1C_9") (pintype "passive"))
    )
    (net (code "97") (name "unconnected-(U2-16{slash}SCL1{slash}RX4{slash}A2-Pad16)") (class "Default")
      (node (ref "U2") (pin "16") (pinfunction "16/SCL1/RX4/A2_16") (pintype "passive"))
    )
    (net (code "98") (name "unconnected-(U2-17{slash}SDA1{slash}TX4{slash}A3-Pad17)") (class "Default")
      (node (ref "U2") (pin "17") (pinfunction "17/SDA1/TX4/A3_17") (pintype "passive"))
    )
    (net (code "99") (name "unconnected-(U2-25{slash}PWM{slash}SDA2{slash}RX6{slash}A11-Pad25)") (class "Default")
      (node (ref "U2") (pin "25") (pinfunction "25/PWM/SDA2/RX6/A11_25") (pintype "passive"))
    )
    (net (code "100") (name "unconnected-(U2-27{slash}SCK1{slash}A13-Pad27)") (class "Default")
      (node (ref "U2") (pin "27") (pinfunction "27/SCK1/A13_27") (pintype "passive"))
    )
    (net (code "101") (name "unconnected-(U2-30{slash}CRX3-Pad30)") (class "Default")
      (node (ref "U2") (pin "30") (pinfunction "30/CRX3_30") (pintype "passive"))
    )
    (net (code "102") (name "unconnected-(U2-31{slash}CTX3-Pad31)") (class "Default")
      (node (ref "U2") (pin "31") (pinfunction "31/CTX3_31") (pintype "passive"))
    )
    (net (code "103") (name "unconnected-(U2-33{slash}PWM{slash}MCLK2-Pad33)") (class "Default")
      (node (ref "U2") (pin "33") (pinfunction "33/PWM/MCLK2_33") (pintype "passive"))
    )
    (net (code "104") (name "unconnected-(U2-34{slash}RX8-Pad34)") (class "Default")
      (node (ref "U2") (pin "34") (pinfunction "34/RX8_34") (pintype "passive"))
    )
    (net (code "105") (name "unconnected-(U2-35{slash}TX8-Pad35)") (class "Default")
      (node (ref "U2") (pin "35") (pinfunction "35/TX8_35") (pintype "passive"))
    )
    (net (code "106") (name "unconnected-(U2-36{slash}PWM{slash}CS-Pad36)") (class "Default")
      (node (ref "U2") (pin "36") (pinfunction "36/PWM/CS_36") (pintype "passive"))
    )
    (net (code "107") (name "unconnected-(U2-40{slash}A16-Pad40)") (class "Default")
      (node (ref "U2") (pin "40") (pinfunction "40/A16_40") (pintype "passive"))
    )
    (net (code "108") (name "unconnected-(U2-41{slash}A17-Pad41)") (class "Default")
      (node (ref "U2") (pin "41") (pinfunction "41/A17_41") (pintype "passive"))
    )
    (net (code "109") (name "unconnected-(U14-INT1-Pad8)") (class "Default")
      (node (ref "U14") (pin "8") (pinfunction "INT1_8") (pintype "passive"))
    )
    (net (code "110") (name "unconnected-(U14-INT2-Pad9)") (class "Default")
      (node (ref "U14") (pin "9") (pinfunction "INT2_9") (pintype "passive"))
    )
    (net (code "111") (name "unconnected-(U16-INT1-Pad8)") (class "Default")
      (node (ref "U16") (pin "8") (pinfunction "INT1_8") (pintype "passive"))
    )
    (net (code "112") (name "unconnected-(U16-INT2-Pad9)") (class "Default")
      (node (ref "U16") (pin "9") (pinfunction "INT2_9") (pintype "passive"))
    )
    (net (code "113") (name "unconnected-(U17-INT1-Pad8)") (class "Default")
      (node (ref "U17") (pin "8") (pinfunction "INT1_8") (pintype "passive"))
    )
    (net (code "114") (name "unconnected-(U17-INT2-Pad9)") (class "Default")
      (node (ref "U17") (pin "9") (pinfunction "INT2_9") (pintype "passive"))
    )
    (net (code "115") (name "unconnected-(U19-INT1-Pad8)") (class "Default")
      (node (ref "U19") (pin "8") (pinfunction "INT1_8") (pintype "passive"))
    )
    (net (code "116") (name "unconnected-(U19-INT2-Pad9)") (class "Default")
      (node (ref "U19") (pin "9") (pinfunction "INT2_9") (pintype "passive"))
    )
    (net (code "117") (name "unconnected-(U22-OFF+-Pad2)") (class "Default")
      (node (ref "U22") (pin "2") (pinfunction "OFF+_2") (pintype "passive"))
    )
  )
)
